# OOBD-Tiger_ISO-CAN.net
KiCad netlist of a schematic drawn in EAGLE
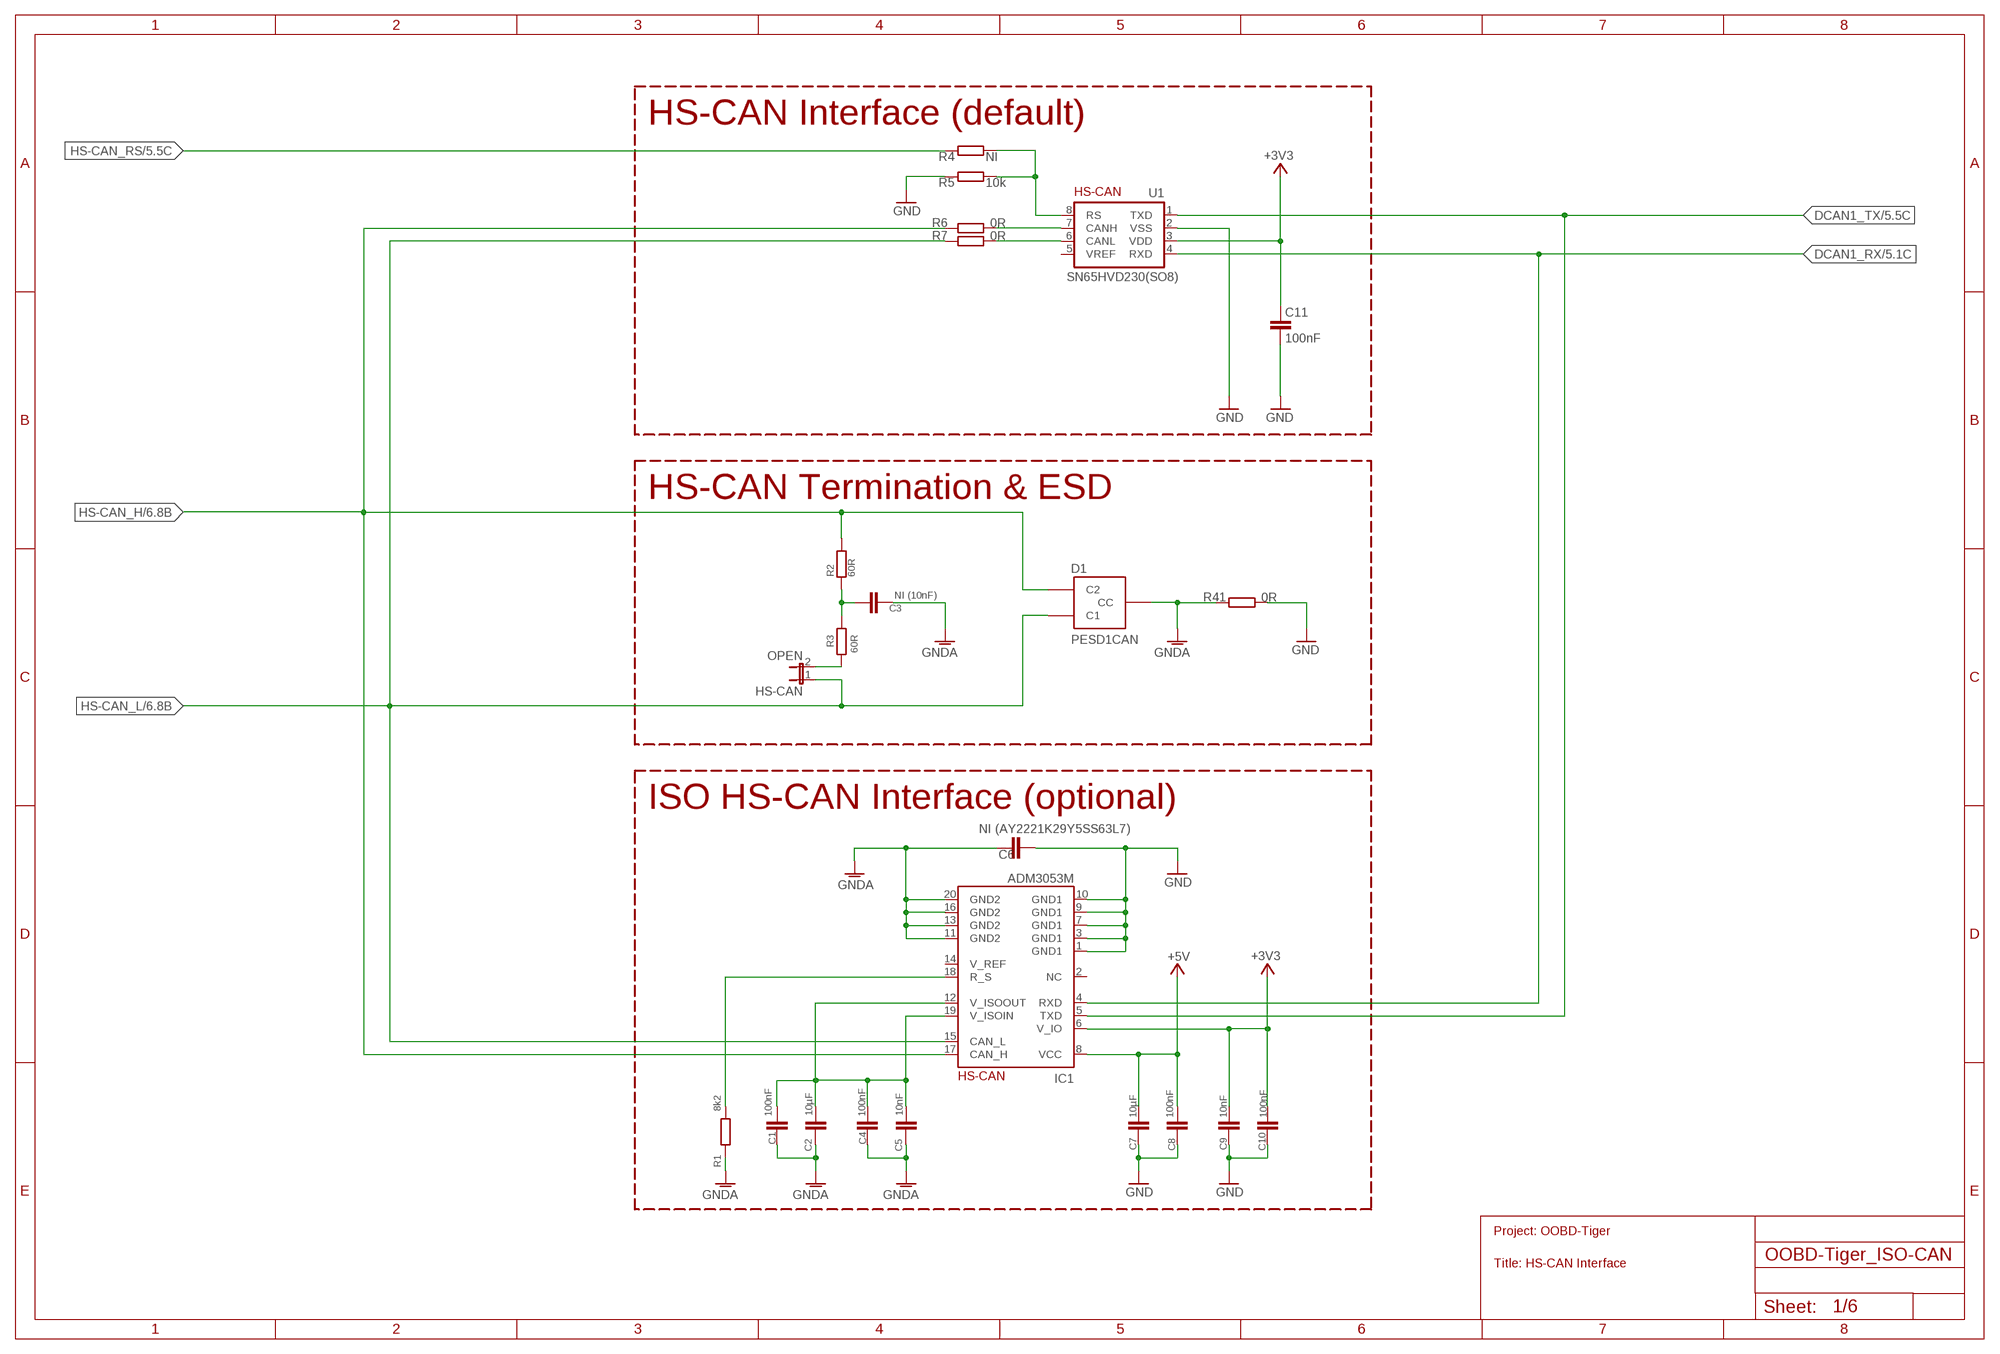
[diagram p0: schematic, sheet 1]
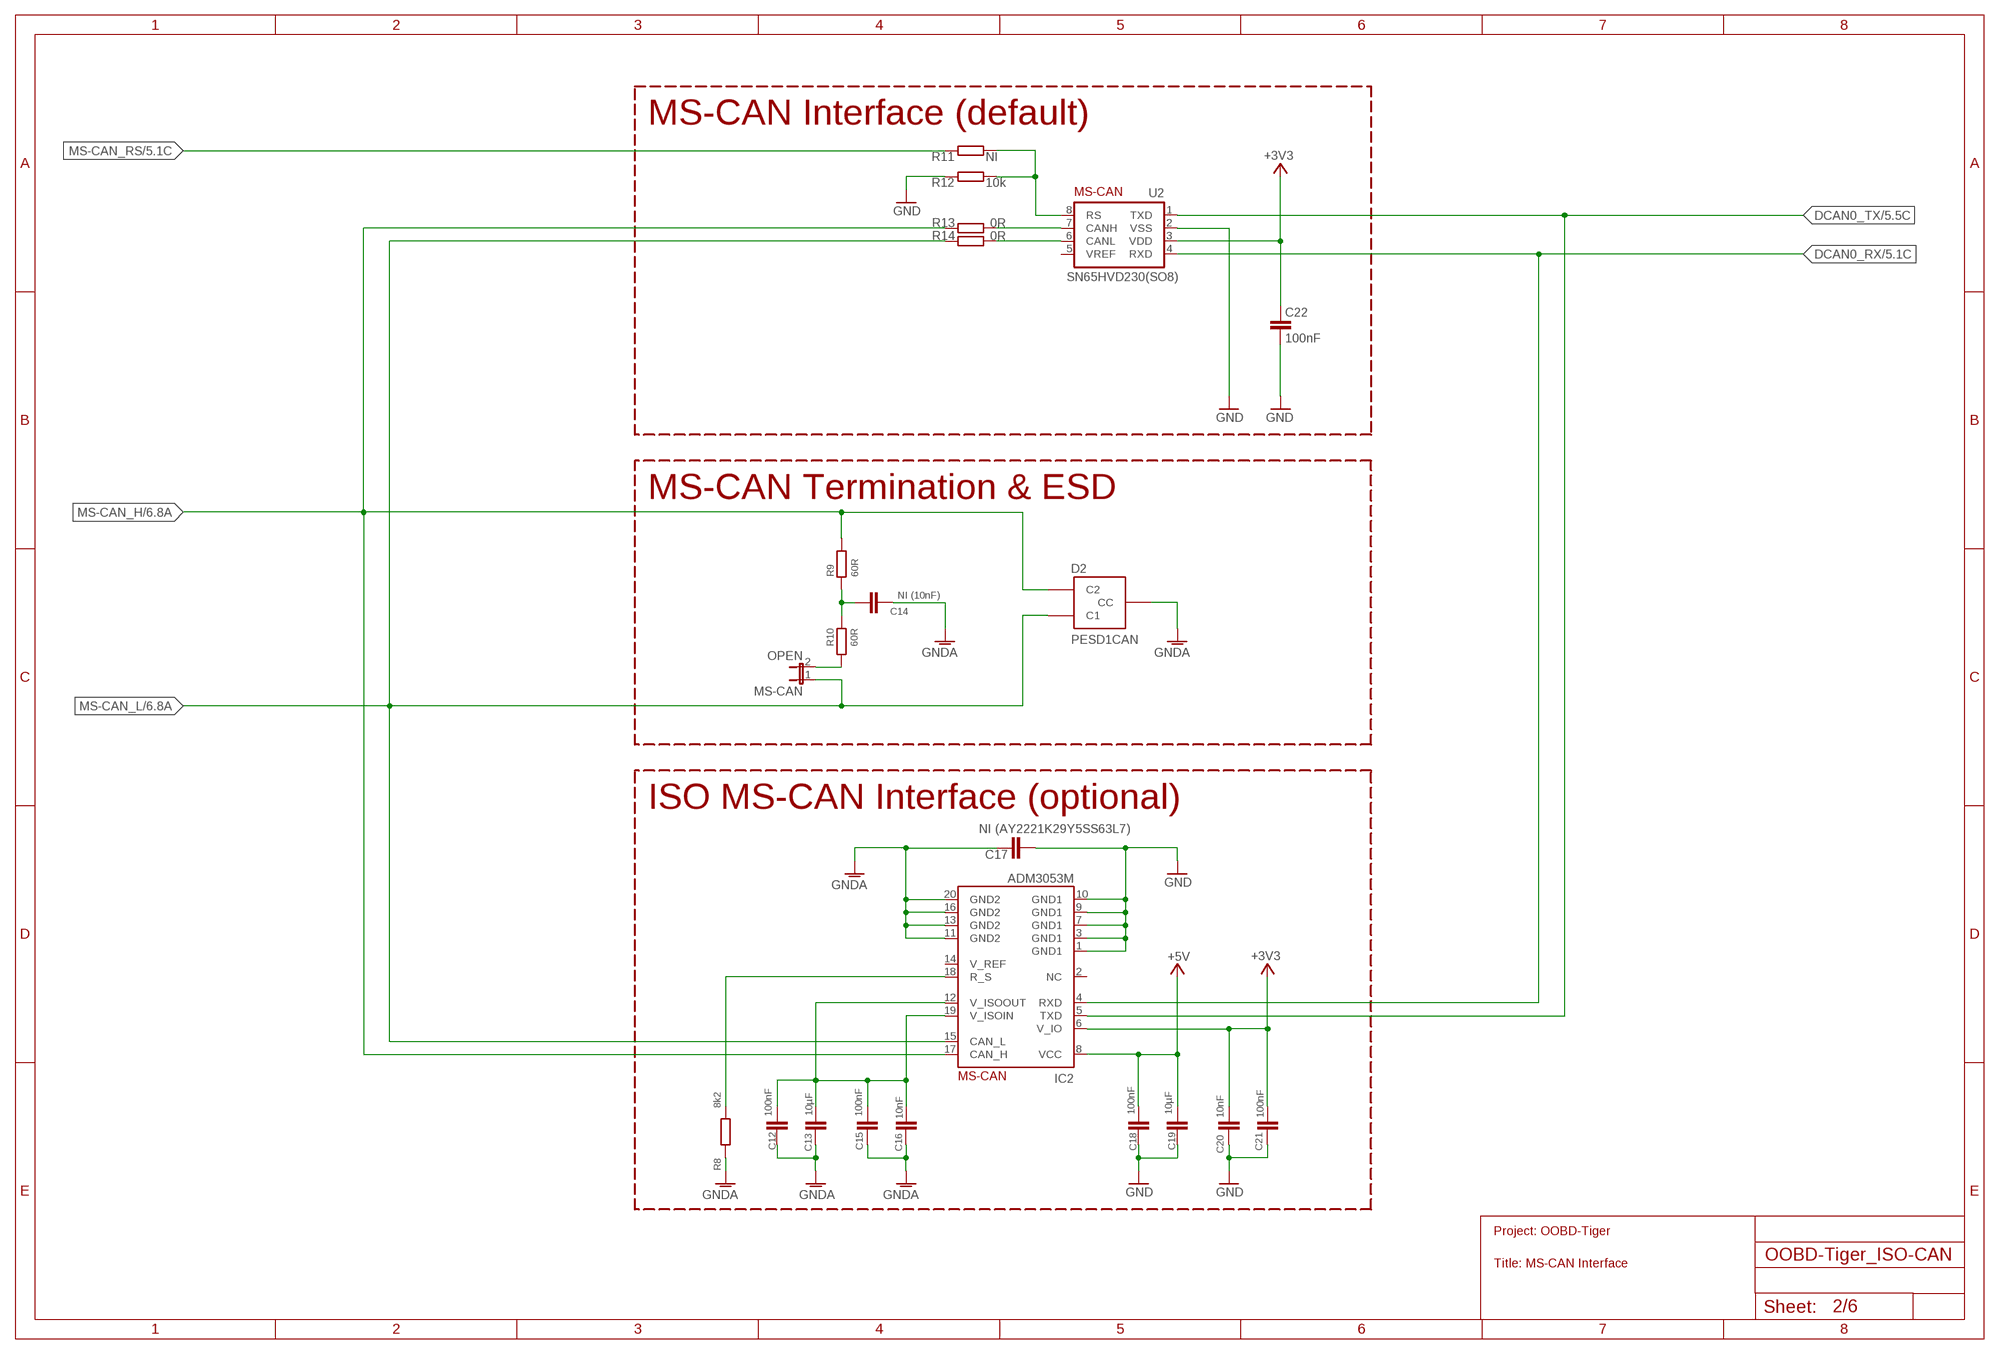
[diagram p1: schematic, sheet 2]
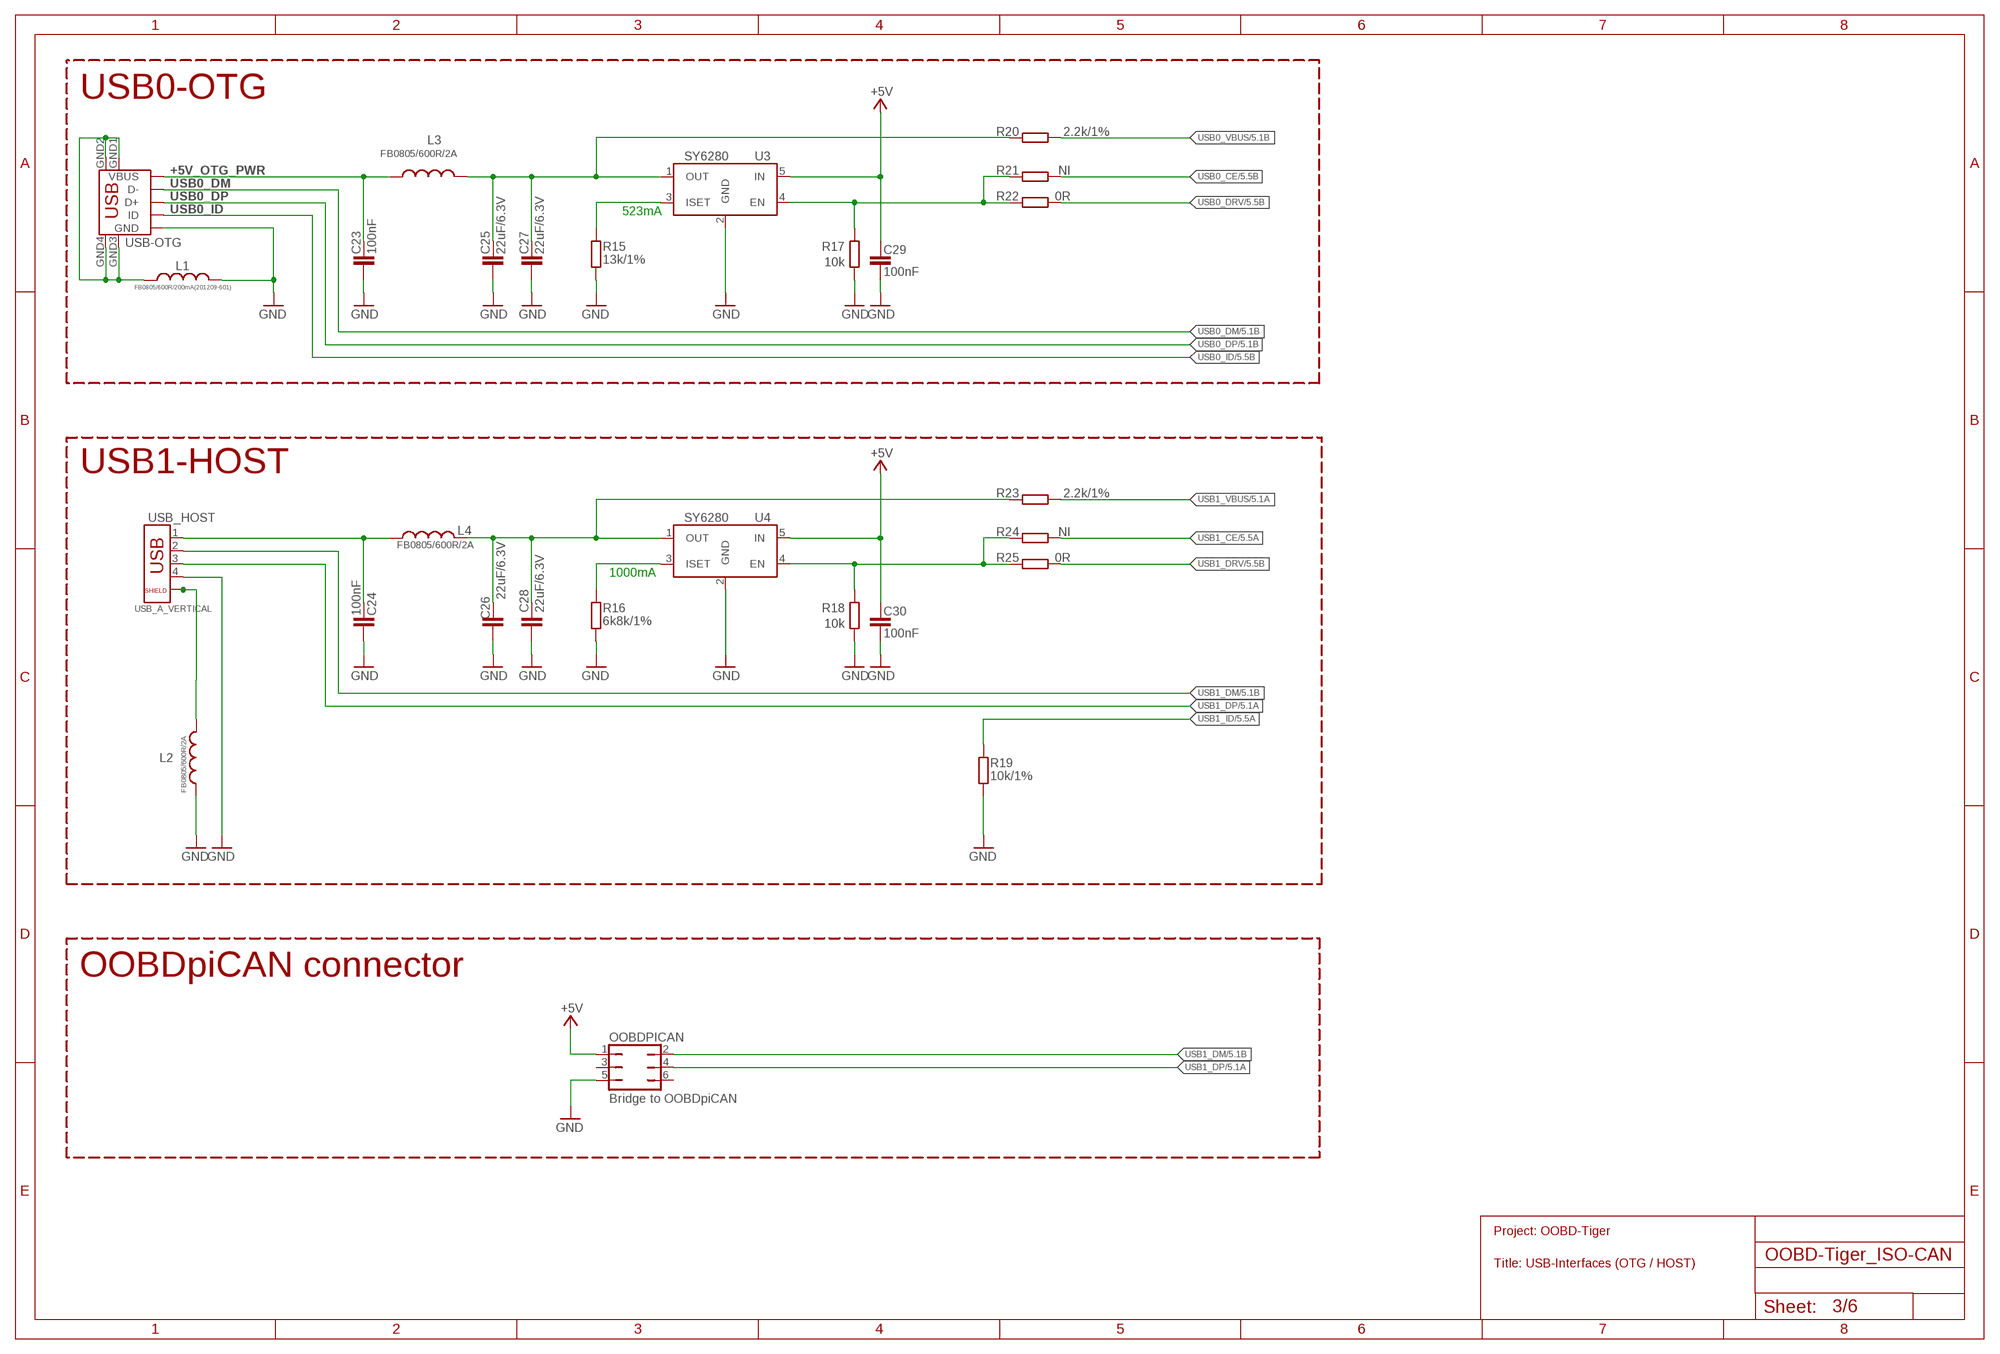
[diagram p2: schematic, sheet 3]
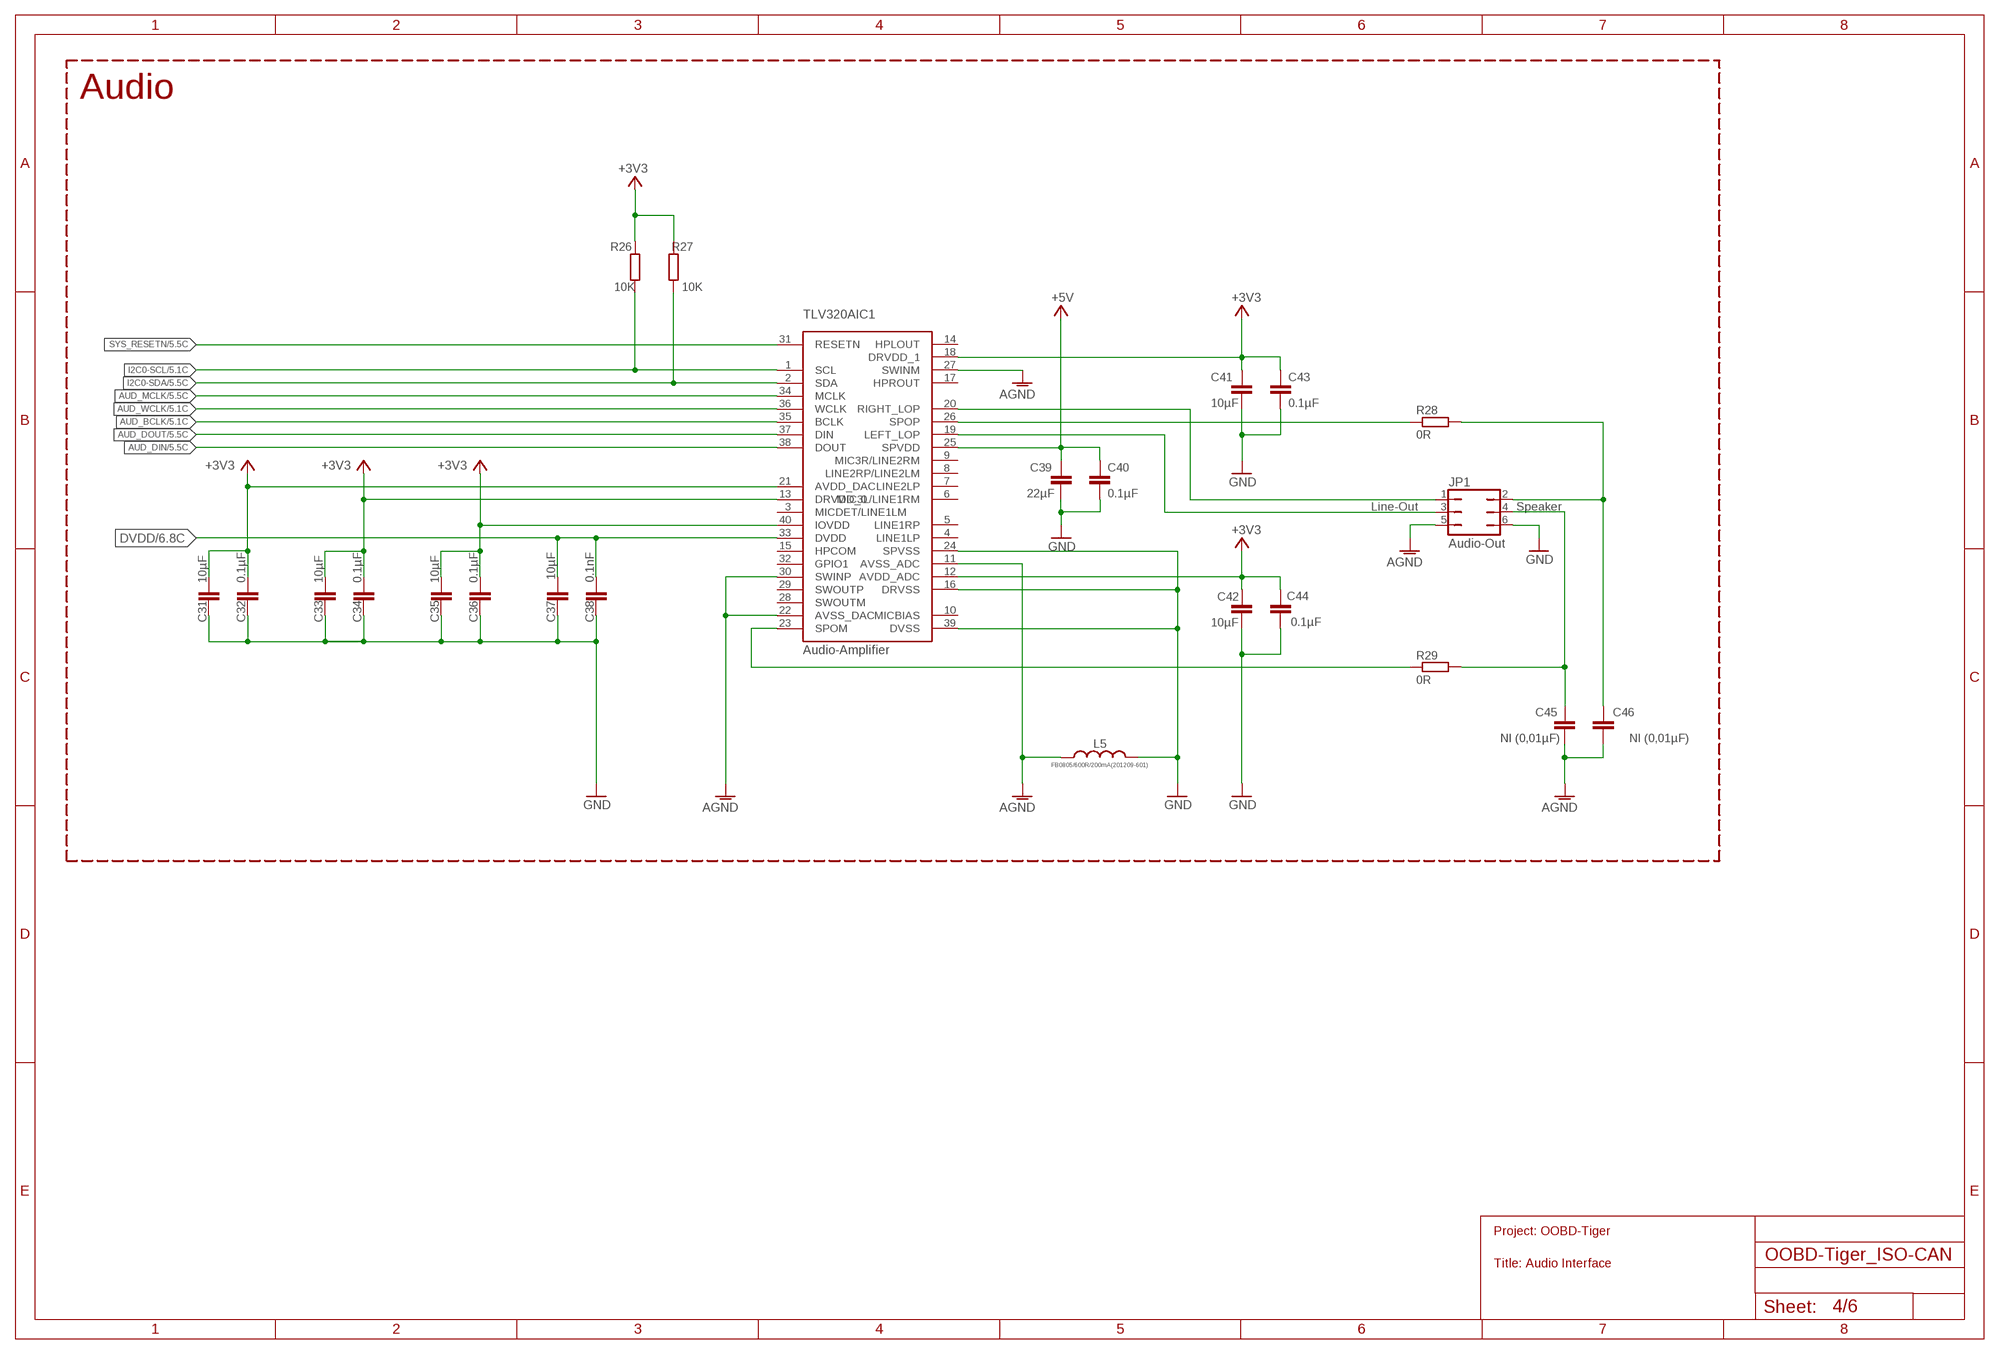
[diagram p3: schematic, sheet 4]
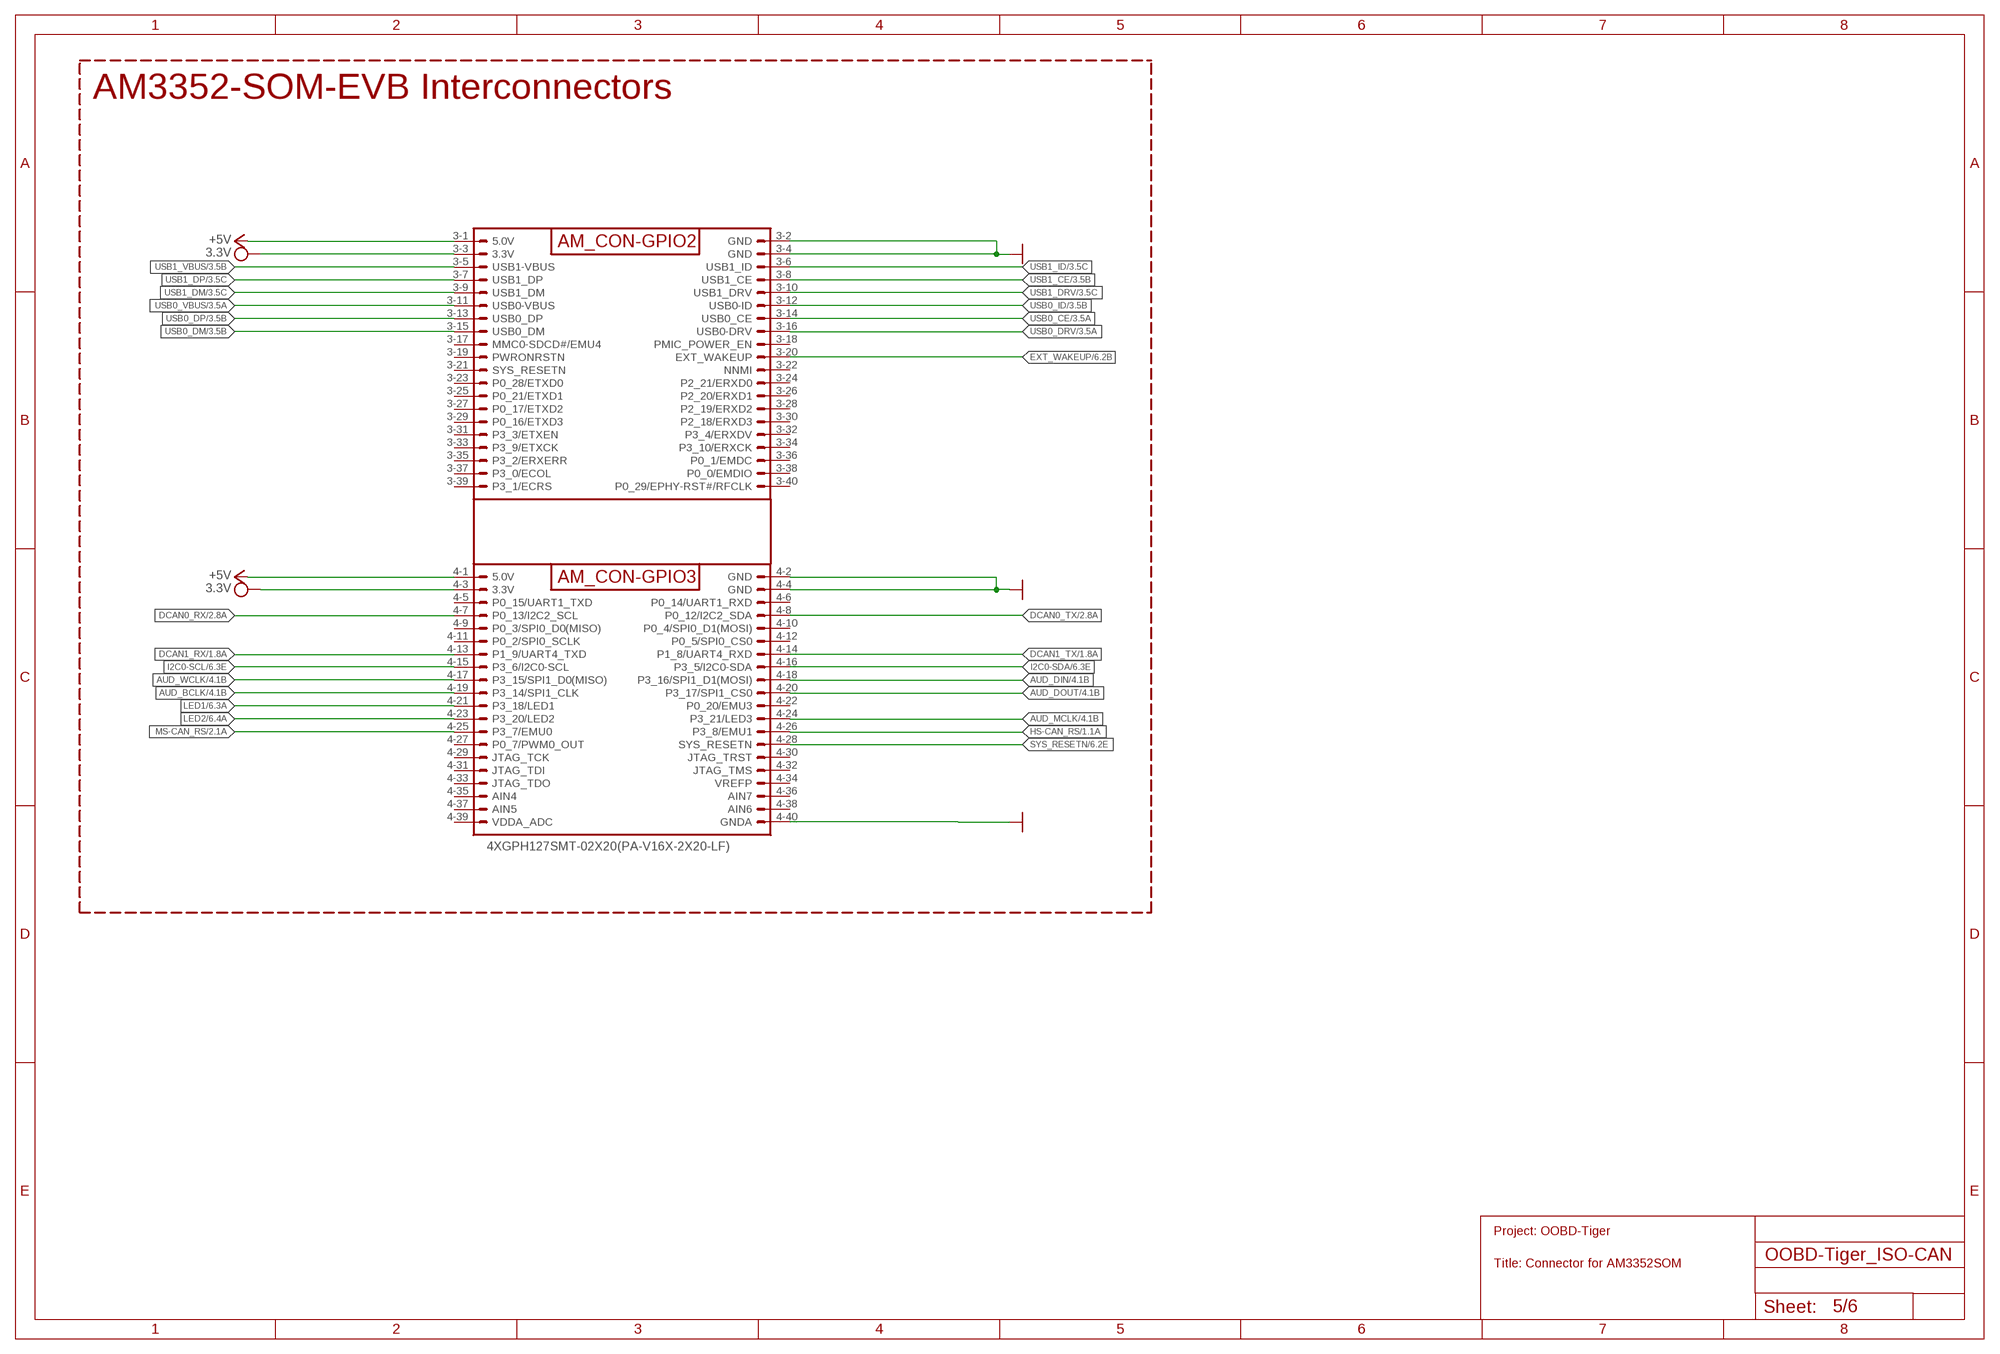
[diagram p4: schematic, sheet 5]
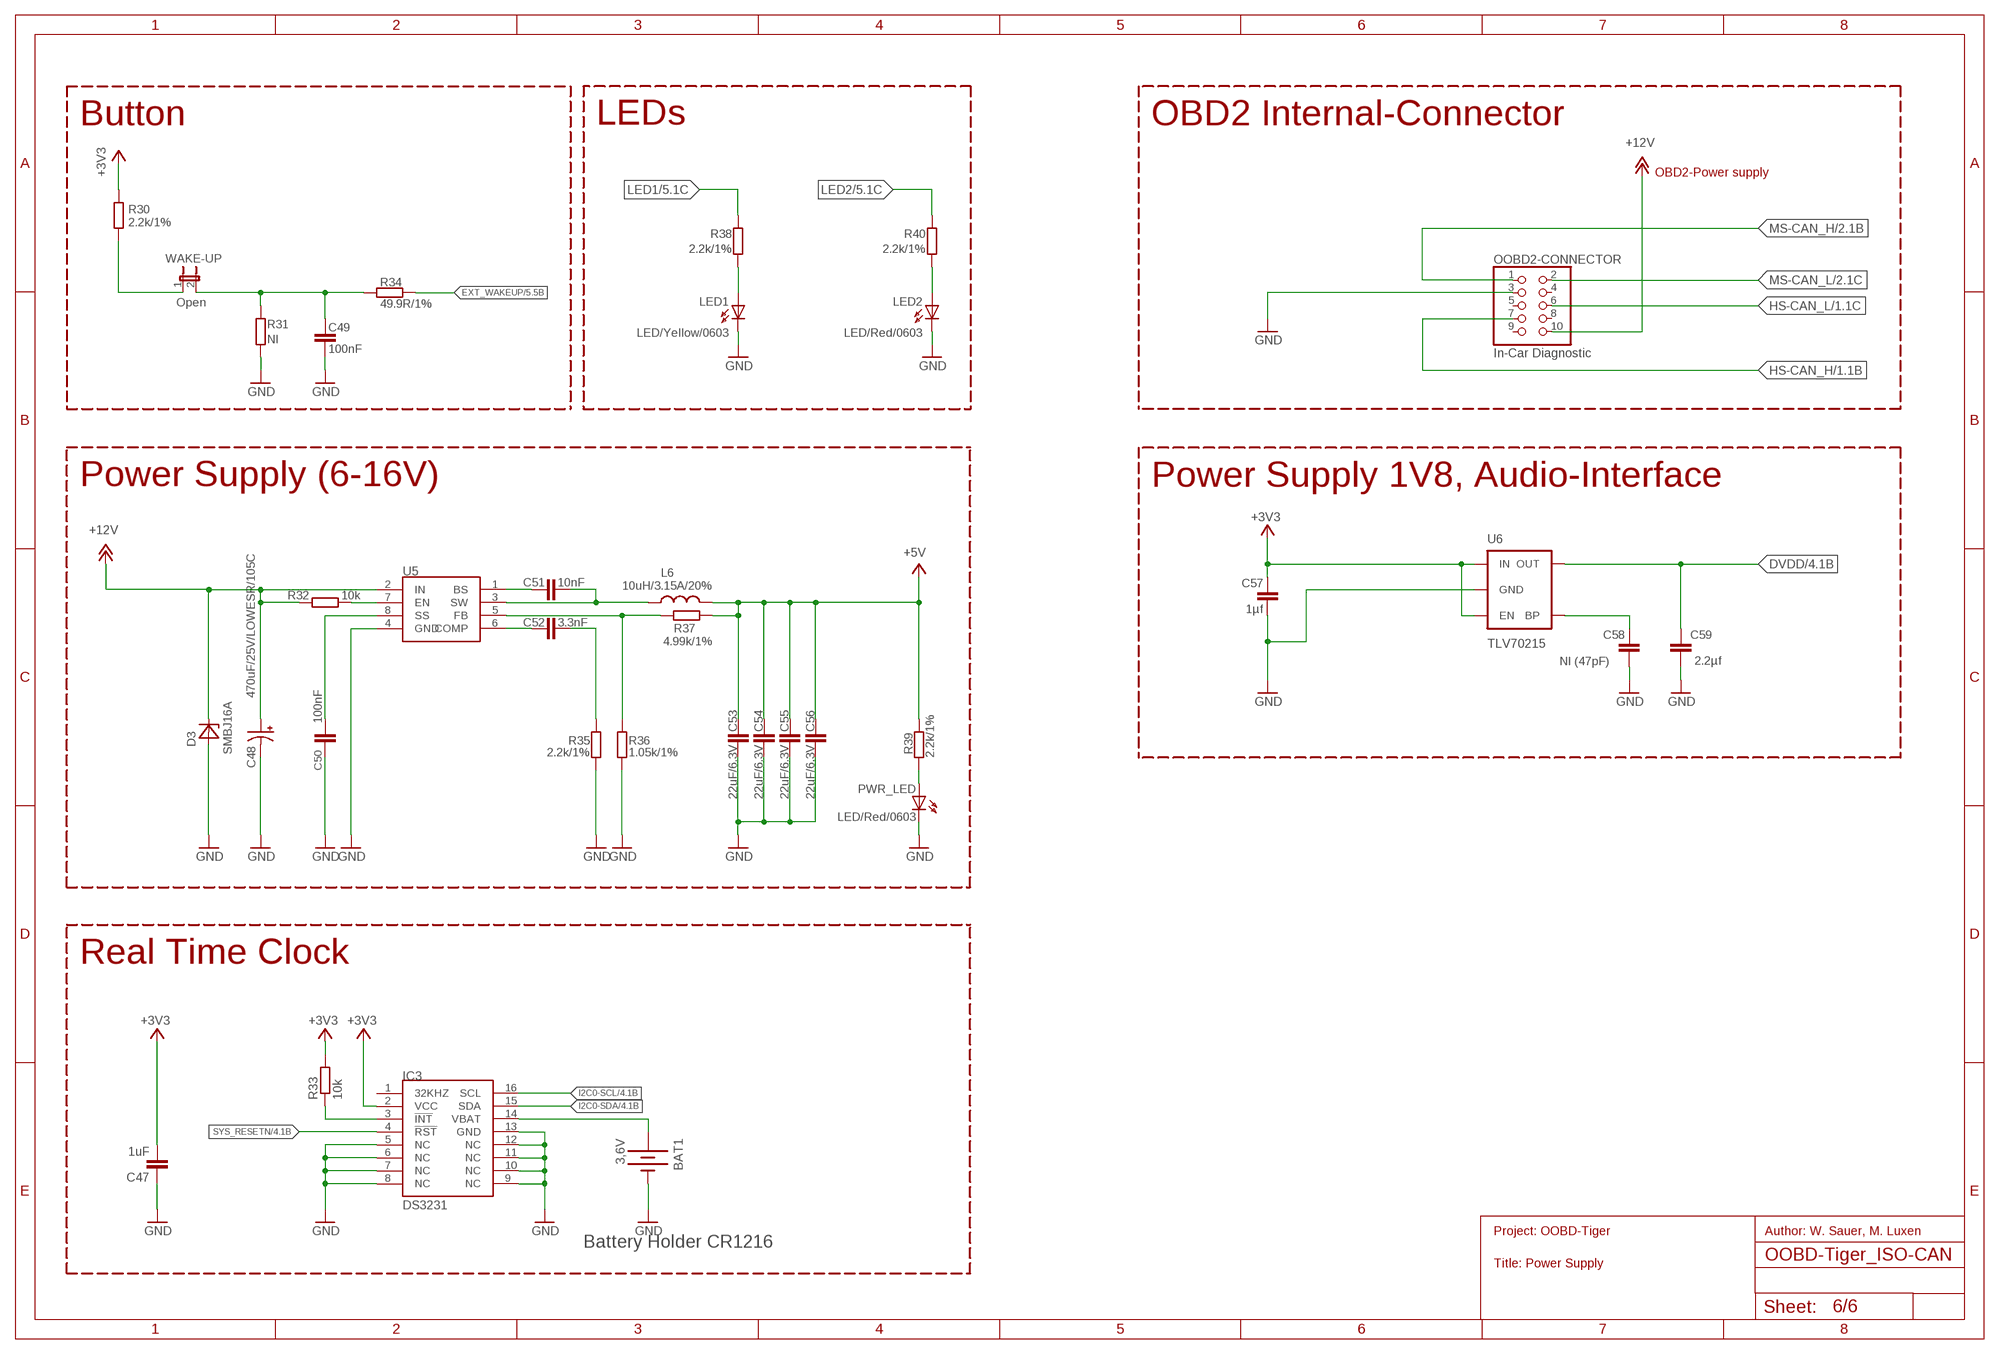
[diagram p5: schematic, sheet 6]

(export (version "E")
  (design (tool "Eeschema 10.0.6"))
  (components
    (comp (ref "C31")
      (value "10µF")
      (footprint "eagle-import:0603-CAP")
      (libsource (lib "eagle-import") (part "CAP0603-CAP"))
    )
    (comp (ref "C32")
      (value "0.1µF")
      (footprint "eagle-import:0603-CAP")
      (libsource (lib "eagle-import") (part "CAP0603-CAP"))
    )
    (comp (ref "C33")
      (value "10µF")
      (footprint "eagle-import:0603-CAP")
      (libsource (lib "eagle-import") (part "CAP0603-CAP"))
    )
    (comp (ref "C34")
      (value "0.1µF")
      (footprint "eagle-import:0603-CAP")
      (libsource (lib "eagle-import") (part "CAP0603-CAP"))
    )
    (comp (ref "C35")
      (value "10µF")
      (footprint "eagle-import:0603-CAP")
      (libsource (lib "eagle-import") (part "CAP0603-CAP"))
    )
    (comp (ref "C36")
      (value "0.1µF")
      (footprint "eagle-import:0603-CAP")
      (libsource (lib "eagle-import") (part "CAP0603-CAP"))
    )
    (comp (ref "C37")
      (value "10µF")
      (footprint "eagle-import:0603-CAP")
      (libsource (lib "eagle-import") (part "CAP0603-CAP"))
    )
    (comp (ref "C38")
      (value "0.1nF")
      (footprint "eagle-import:0603-CAP")
      (libsource (lib "eagle-import") (part "CAP0603-CAP"))
    )
    (comp (ref "C39")
      (value "22µF")
      (footprint "eagle-import:0603-CAP")
      (libsource (lib "eagle-import") (part "CAP0603-CAP"))
    )
    (comp (ref "C40")
      (value "0.1µF")
      (footprint "eagle-import:0603-CAP")
      (libsource (lib "eagle-import") (part "CAP0603-CAP"))
    )
    (comp (ref "C41")
      (value "10µF")
      (footprint "eagle-import:0603-CAP")
      (libsource (lib "eagle-import") (part "CAP0603-CAP"))
    )
    (comp (ref "C42")
      (value "10µF")
      (footprint "eagle-import:0603-CAP")
      (libsource (lib "eagle-import") (part "CAP0603-CAP"))
    )
    (comp (ref "C43")
      (value "0.1µF")
      (footprint "eagle-import:0603-CAP")
      (libsource (lib "eagle-import") (part "CAP0603-CAP"))
    )
    (comp (ref "C44")
      (value "0.1µF")
      (footprint "eagle-import:0603-CAP")
      (libsource (lib "eagle-import") (part "CAP0603-CAP"))
    )
    (comp (ref "C45")
      (value "NI (0,01µF)")
      (footprint "eagle-import:0603-CAP")
      (libsource (lib "eagle-import") (part "CAP0603-CAP"))
    )
    (comp (ref "C46")
      (value "NI (0,01µF)")
      (footprint "eagle-import:0603-CAP")
      (libsource (lib "eagle-import") (part "CAP0603-CAP"))
    )
    (comp (ref "JP1")
      (value "Audio-Out")
      (footprint "eagle-import:JP3Q")
      (libsource (lib "eagle-import") (part "JP3Q"))
    )
    (comp (ref "L5")
      (value "FB0805/600R/200mA(201209-601)")
      (footprint "eagle-import:L0603")
      (libsource (lib "eagle-import") (part "L-USL0603"))
    )
    (comp (ref "R26")
      (value "10K")
      (footprint "eagle-import:R0603")
      (libsource (lib "eagle-import") (part "resistor_R-EU_R0603"))
    )
    (comp (ref "R27")
      (value "10K")
      (footprint "eagle-import:R0603")
      (libsource (lib "eagle-import") (part "resistor_R-EU_R0603"))
    )
    (comp (ref "R28")
      (value "0R")
      (footprint "eagle-import:R0805")
      (libsource (lib "eagle-import") (part "resistor_R-EU_R0805"))
    )
    (comp (ref "R29")
      (value "0R")
      (footprint "eagle-import:R0805")
      (libsource (lib "eagle-import") (part "resistor_R-EU_R0805"))
    )
    (comp (ref "TLV320AIC1")
      (value "Audio-Amplifier")
      (footprint "eagle-import:QFN40-6X6")
      (libsource (lib "eagle-import") (part "TLV320AIC3107"))
    )
    (comp (ref "C1")
      (value "100nF")
      (footprint "eagle-import:C0603K")
      (libsource (lib "eagle-import") (part "C-EUC0603K"))
    )
    (comp (ref "C2")
      (value "10µF")
      (footprint "eagle-import:C0805K")
      (libsource (lib "eagle-import") (part "C-EUC0805K"))
    )
    (comp (ref "C3")
      (value "NI (10nF)")
      (footprint "eagle-import:C0603")
      (libsource (lib "eagle-import") (part "resistor_C-EUC0603"))
    )
    (comp (ref "C4")
      (value "100nF")
      (footprint "eagle-import:C0603K")
      (libsource (lib "eagle-import") (part "C-EUC0603K"))
    )
    (comp (ref "C5")
      (value "10nF")
      (footprint "eagle-import:C0805K")
      (libsource (lib "eagle-import") (part "C-EUC0805K"))
    )
    (comp (ref "C6")
      (value "NI (AY2221K29Y5SS63L7)")
      (footprint "eagle-import:C075-032X103")
      (libsource (lib "eagle-import") (part "C-EU075-032X103"))
    )
    (comp (ref "C7")
      (value "10µF")
      (footprint "eagle-import:C0805K")
      (libsource (lib "eagle-import") (part "C-EUC0805K"))
    )
    (comp (ref "C8")
      (value "100nF")
      (footprint "eagle-import:C0603K")
      (libsource (lib "eagle-import") (part "C-EUC0603K"))
    )
    (comp (ref "C9")
      (value "10nF")
      (footprint "eagle-import:C0805K")
      (libsource (lib "eagle-import") (part "C-EUC0805K"))
    )
    (comp (ref "C10")
      (value "100nF")
      (footprint "eagle-import:C0603K")
      (libsource (lib "eagle-import") (part "C-EUC0603K"))
    )
    (comp (ref "C11")
      (value "100nF")
      (footprint "eagle-import:C0603K")
      (libsource (lib "eagle-import") (part "C-EUC0603K"))
    )
    (comp (ref "D1")
      (value "PESD1CAN")
      (footprint "eagle-import:SOT23")
      (libsource (lib "eagle-import") (part "PESD1CAN"))
    )
    (comp (ref "HS-CAN")
      (value "OPEN")
      (footprint "eagle-import:1X02")
      (libsource (lib "eagle-import") (part "JUMPER-2PTH"))
    )
    (comp (ref "IC1")
      (value "ADM3053M")
      (footprint "eagle-import:SO20W")
      (libsource (lib "eagle-import") (part "ADM3053M"))
    )
    (comp (ref "R1")
      (value "8k2")
      (footprint "eagle-import:R0603")
      (libsource (lib "eagle-import") (part "R-EU_R0603"))
    )
    (comp (ref "R2")
      (value "60R")
      (footprint "eagle-import:R0603")
      (libsource (lib "eagle-import") (part "resistor_R-EU_R0603"))
    )
    (comp (ref "R3")
      (value "60R")
      (footprint "eagle-import:R0603")
      (libsource (lib "eagle-import") (part "resistor_R-EU_R0603"))
    )
    (comp (ref "R4")
      (value "NI")
      (footprint "eagle-import:R0603")
      (libsource (lib "eagle-import") (part "R-EU_R0603"))
    )
    (comp (ref "R5")
      (value "10k")
      (footprint "eagle-import:R0603")
      (libsource (lib "eagle-import") (part "R-EU_R0603"))
    )
    (comp (ref "R6")
      (value "0R")
      (footprint "eagle-import:0207_10")
      (libsource (lib "eagle-import") (part "R-EU_0207/10"))
    )
    (comp (ref "R7")
      (value "0R")
      (footprint "eagle-import:0207_10")
      (libsource (lib "eagle-import") (part "R-EU_0207/10"))
    )
    (comp (ref "R41")
      (value "0R")
      (footprint "eagle-import:0207_10")
      (libsource (lib "eagle-import") (part "R-EU_0207/10"))
    )
    (comp (ref "U1")
      (value "SN65HVD230(SO8)")
      (footprint "eagle-import:SO-08")
      (libsource (lib "eagle-import") (part "MCP2551"))
    )
    (comp (ref "C23")
      (value "100nF")
      (footprint "eagle-import:C0603K")
      (libsource (lib "eagle-import") (part "C-EUC0603K"))
    )
    (comp (ref "C24")
      (value "100nF")
      (footprint "eagle-import:C0603K")
      (libsource (lib "eagle-import") (part "C-EUC0603K"))
    )
    (comp (ref "C25")
      (value "22uF/6.3V")
      (footprint "eagle-import:C0603")
      (libsource (lib "eagle-import") (part "C-EUC0603"))
    )
    (comp (ref "C26")
      (value "22uF/6.3V")
      (footprint "eagle-import:C0603")
      (libsource (lib "eagle-import") (part "C-EUC0603"))
    )
    (comp (ref "C27")
      (value "22uF/6.3V")
      (footprint "eagle-import:C0603")
      (libsource (lib "eagle-import") (part "C-EUC0603"))
    )
    (comp (ref "C28")
      (value "22uF/6.3V")
      (footprint "eagle-import:C0603")
      (libsource (lib "eagle-import") (part "C-EUC0603"))
    )
    (comp (ref "C29")
      (value "100nF")
      (footprint "eagle-import:C0603K")
      (libsource (lib "eagle-import") (part "C-EUC0603K"))
    )
    (comp (ref "C30")
      (value "100nF")
      (footprint "eagle-import:C0603K")
      (libsource (lib "eagle-import") (part "C-EUC0603K"))
    )
    (comp (ref "L1")
      (value "FB0805/600R/200mA(201209-601)")
      (footprint "eagle-import:L0603")
      (libsource (lib "eagle-import") (part "L-USL0603"))
    )
    (comp (ref "L2")
      (value "FB0805/600R/2A")
      (footprint "eagle-import:L0603")
      (libsource (lib "eagle-import") (part "L-USL0603"))
    )
    (comp (ref "L3")
      (value "FB0805/600R/2A")
      (footprint "eagle-import:L0603")
      (libsource (lib "eagle-import") (part "L-USL0603"))
    )
    (comp (ref "L4")
      (value "FB0805/600R/2A")
      (footprint "eagle-import:L0603")
      (libsource (lib "eagle-import") (part "L-USL0603"))
    )
    (comp (ref "OOBDPICAN")
      (value "Bridge to OOBDpiCAN")
      (footprint "eagle-import:JP3Q")
      (libsource (lib "eagle-import") (part "JP3Q"))
    )
    (comp (ref "R15")
      (value "13k/1%")
      (footprint "eagle-import:R0603")
      (libsource (lib "eagle-import") (part "R-EU_R0603"))
    )
    (comp (ref "R16")
      (value "6k8k/1%")
      (footprint "eagle-import:R0603")
      (libsource (lib "eagle-import") (part "R-EU_R0603"))
    )
    (comp (ref "R17")
      (value "10k")
      (footprint "eagle-import:R0603")
      (libsource (lib "eagle-import") (part "R-EU_R0603"))
    )
    (comp (ref "R18")
      (value "10k")
      (footprint "eagle-import:R0603")
      (libsource (lib "eagle-import") (part "R-EU_R0603"))
    )
    (comp (ref "R19")
      (value "10k/1%")
      (footprint "eagle-import:R0603")
      (libsource (lib "eagle-import") (part "R-EU_R0603"))
    )
    (comp (ref "R20")
      (value "2.2k/1%")
      (footprint "eagle-import:R0603")
      (libsource (lib "eagle-import") (part "R-EU_R0603"))
    )
    (comp (ref "R21")
      (value "NI")
      (footprint "eagle-import:R0603")
      (libsource (lib "eagle-import") (part "R-EU_R0603"))
    )
    (comp (ref "R22")
      (value "0R")
      (footprint "eagle-import:R0603")
      (libsource (lib "eagle-import") (part "R-EU_R0603"))
    )
    (comp (ref "R23")
      (value "2.2k/1%")
      (footprint "eagle-import:R0603")
      (libsource (lib "eagle-import") (part "R-EU_R0603"))
    )
    (comp (ref "R24")
      (value "NI")
      (footprint "eagle-import:R0603")
      (libsource (lib "eagle-import") (part "R-EU_R0603"))
    )
    (comp (ref "R25")
      (value "0R")
      (footprint "eagle-import:R0603")
      (libsource (lib "eagle-import") (part "R-EU_R0603"))
    )
    (comp (ref "U3")
      (value "SY6280")
      (footprint "eagle-import:SOT23-5")
      (libsource (lib "eagle-import") (part "SY6280"))
    )
    (comp (ref "U4")
      (value "SY6280")
      (footprint "eagle-import:SOT23-5")
      (libsource (lib "eagle-import") (part "SY6280"))
    )
    (comp (ref "USB_HOST")
      (value "USB_A_VERTICAL")
      (footprint "eagle-import:USB_PN87520_DEV_PTH")
      (libsource (lib "eagle-import") (part "USB_SHIELD1"))
    )
    (comp (ref "USB_OTG")
      (value "USB-OTG")
      (footprint "eagle-import:USB_MINI_9PIN")
      (libsource (lib "eagle-import") (part "MINI_USB9"))
    )
    (comp (ref "C12")
      (value "100nF")
      (footprint "eagle-import:C0603K")
      (libsource (lib "eagle-import") (part "C-EUC0603K"))
    )
    (comp (ref "C13")
      (value "10µF")
      (footprint "eagle-import:C0805K")
      (libsource (lib "eagle-import") (part "C-EUC0805K"))
    )
    (comp (ref "C14")
      (value "NI (10nF)")
      (footprint "eagle-import:C0603")
      (libsource (lib "eagle-import") (part "resistor_C-EUC0603"))
    )
    (comp (ref "C15")
      (value "100nF")
      (footprint "eagle-import:C0603K")
      (libsource (lib "eagle-import") (part "C-EUC0603K"))
    )
    (comp (ref "C16")
      (value "10nF")
      (footprint "eagle-import:C0805K")
      (libsource (lib "eagle-import") (part "C-EUC0805K"))
    )
    (comp (ref "C17")
      (value "NI (AY2221K29Y5SS63L7)")
      (footprint "eagle-import:C075-032X103")
      (libsource (lib "eagle-import") (part "C-EU075-032X103"))
    )
    (comp (ref "C18")
      (value "100nF")
      (footprint "eagle-import:C0603K")
      (libsource (lib "eagle-import") (part "C-EUC0603K"))
    )
    (comp (ref "C19")
      (value "10µF")
      (footprint "eagle-import:C0805K")
      (libsource (lib "eagle-import") (part "C-EUC0805K"))
    )
    (comp (ref "C20")
      (value "10nF")
      (footprint "eagle-import:C0805K")
      (libsource (lib "eagle-import") (part "C-EUC0805K"))
    )
    (comp (ref "C21")
      (value "100nF")
      (footprint "eagle-import:C0603K")
      (libsource (lib "eagle-import") (part "C-EUC0603K"))
    )
    (comp (ref "C22")
      (value "100nF")
      (footprint "eagle-import:C0603K")
      (libsource (lib "eagle-import") (part "C-EUC0603K"))
    )
    (comp (ref "D2")
      (value "PESD1CAN")
      (footprint "eagle-import:SOT23")
      (libsource (lib "eagle-import") (part "PESD1CAN"))
    )
    (comp (ref "IC2")
      (value "ADM3053M")
      (footprint "eagle-import:SO20W")
      (libsource (lib "eagle-import") (part "ADM3053M"))
    )
    (comp (ref "MS-CAN")
      (value "OPEN")
      (footprint "eagle-import:1X02")
      (libsource (lib "eagle-import") (part "JUMPER-2PTH"))
    )
    (comp (ref "R8")
      (value "8k2")
      (footprint "eagle-import:R0603")
      (libsource (lib "eagle-import") (part "R-EU_R0603"))
    )
    (comp (ref "R9")
      (value "60R")
      (footprint "eagle-import:R0603")
      (libsource (lib "eagle-import") (part "resistor_R-EU_R0603"))
    )
    (comp (ref "R10")
      (value "60R")
      (footprint "eagle-import:R0603")
      (libsource (lib "eagle-import") (part "resistor_R-EU_R0603"))
    )
    (comp (ref "R11")
      (value "NI")
      (footprint "eagle-import:R0603")
      (libsource (lib "eagle-import") (part "R-EU_R0603"))
    )
    (comp (ref "R12")
      (value "10k")
      (footprint "eagle-import:R0603")
      (libsource (lib "eagle-import") (part "R-EU_R0603"))
    )
    (comp (ref "R13")
      (value "0R")
      (footprint "eagle-import:0207_10")
      (libsource (lib "eagle-import") (part "R-EU_0207/10"))
    )
    (comp (ref "R14")
      (value "0R")
      (footprint "eagle-import:0207_10")
      (libsource (lib "eagle-import") (part "R-EU_0207/10"))
    )
    (comp (ref "U2")
      (value "SN65HVD230(SO8)")
      (footprint "eagle-import:SO-08")
      (libsource (lib "eagle-import") (part "MCP2551"))
    )
    (comp (ref "BAT1")
      (value "3,6V")
      (footprint "eagle-import:BATTCON_12MM_PTH")
      (libsource (lib "eagle-import") (part "BATTERY12PTH"))
    )
    (comp (ref "C47")
      (value "1uF")
      (footprint "eagle-import:C0603")
      (libsource (lib "eagle-import") (part "C-EUC0603"))
    )
    (comp (ref "C48")
      (value "470uF/25V/LOWESR/105C")
      (footprint "eagle-import:PANASONIC_D")
      (libsource (lib "eagle-import") (part "47UF-50V-20%(ELECT)"))
    )
    (comp (ref "C49")
      (value "100nF")
      (footprint "eagle-import:C0603")
      (libsource (lib "eagle-import") (part "C-EUC0603"))
    )
    (comp (ref "C50")
      (value "100nF")
      (footprint "eagle-import:C0603")
      (libsource (lib "eagle-import") (part "C-EUC0603"))
    )
    (comp (ref "C51")
      (value "10nF")
      (footprint "eagle-import:C0603")
      (libsource (lib "eagle-import") (part "C-EUC0603"))
    )
    (comp (ref "C52")
      (value "3.3nF")
      (footprint "eagle-import:C0603")
      (libsource (lib "eagle-import") (part "C-EUC0603"))
    )
    (comp (ref "C53")
      (value "22uF/6.3V")
      (footprint "eagle-import:C0603")
      (libsource (lib "eagle-import") (part "C-EUC0603"))
    )
    (comp (ref "C54")
      (value "22uF/6.3V")
      (footprint "eagle-import:C0603")
      (libsource (lib "eagle-import") (part "C-EUC0603"))
    )
    (comp (ref "C55")
      (value "22uF/6.3V")
      (footprint "eagle-import:C0603")
      (libsource (lib "eagle-import") (part "C-EUC0603"))
    )
    (comp (ref "C56")
      (value "22uF/6.3V")
      (footprint "eagle-import:C0603")
      (libsource (lib "eagle-import") (part "C-EUC0603"))
    )
    (comp (ref "C57")
      (value "1µf")
      (footprint "eagle-import:0603-CAP")
      (libsource (lib "eagle-import") (part "CAP0603-CAP"))
    )
    (comp (ref "C58")
      (value "NI (47pF)")
      (footprint "eagle-import:0603-CAP")
      (libsource (lib "eagle-import") (part "CAP0603-CAP"))
    )
    (comp (ref "C59")
      (value "2.2µf")
      (footprint "eagle-import:0603-CAP")
      (libsource (lib "eagle-import") (part "CAP0603-CAP"))
    )
    (comp (ref "D3")
      (value "SMBJ16A")
      (footprint "eagle-import:DO214AA")
      (libsource (lib "eagle-import") (part "SMBJ16A"))
    )
    (comp (ref "IC3")
      (value "DS3231")
      (footprint "eagle-import:SOIC-16W")
      (libsource (lib "eagle-import") (part "DS3231SOIC-16W"))
    )
    (comp (ref "L6")
      (value "10uH/3.15A/20%")
      (footprint "eagle-import:8X8MM_3131")
      (libsource (lib "eagle-import") (part "LLQH88PN100M38"))
    )
    (comp (ref "LED1")
      (value "LED/Yellow/0603")
      (footprint "eagle-import:LED_0603")
      (libsource (lib "eagle-import") (part "LEDLED_0603"))
    )
    (comp (ref "LED2")
      (value "LED/Red/0603")
      (footprint "eagle-import:LED_0603")
      (libsource (lib "eagle-import") (part "LEDLED_0603"))
    )
    (comp (ref "OOBD2-CONNECTOR")
      (value "In-Car Diagnostic")
      (footprint "eagle-import:2X05_90")
      (libsource (lib "eagle-import") (part "PINHD-2X5/90"))
    )
    (comp (ref "PWR_LED")
      (value "LED/Red/0603")
      (footprint "eagle-import:LED-0603")
      (libsource (lib "eagle-import") (part "LED0603DWS"))
    )
    (comp (ref "R30")
      (value "2.2k/1%")
      (footprint "eagle-import:R0603")
      (libsource (lib "eagle-import") (part "R-EU_R0603"))
    )
    (comp (ref "R31")
      (value "NI")
      (footprint "eagle-import:R0603")
      (libsource (lib "eagle-import") (part "R-EU_R0603"))
    )
    (comp (ref "R32")
      (value "10k")
      (footprint "eagle-import:R0603")
      (libsource (lib "eagle-import") (part "R-EU_R0603"))
    )
    (comp (ref "R33")
      (value "10k")
      (footprint "eagle-import:R0603")
      (libsource (lib "eagle-import") (part "R-EU_R0603"))
    )
    (comp (ref "R34")
      (value "49.9R/1%")
      (footprint "eagle-import:R0603")
      (libsource (lib "eagle-import") (part "R-EU_R0603"))
    )
    (comp (ref "R35")
      (value "2.2k/1%")
      (footprint "eagle-import:R0603")
      (libsource (lib "eagle-import") (part "R-EU_R0603"))
    )
    (comp (ref "R36")
      (value "1.05k/1%")
      (footprint "eagle-import:R0603")
      (libsource (lib "eagle-import") (part "R-EU_R0603"))
    )
    (comp (ref "R37")
      (value "4.99k/1%")
      (footprint "eagle-import:R0603")
      (libsource (lib "eagle-import") (part "R-EU_R0603"))
    )
    (comp (ref "R38")
      (value "2.2k/1%")
      (footprint "eagle-import:R0603")
      (libsource (lib "eagle-import") (part "R-EU_R0603"))
    )
    (comp (ref "R39")
      (value "2.2k/1%")
      (footprint "eagle-import:R0603")
      (libsource (lib "eagle-import") (part "R-EU_R0603"))
    )
    (comp (ref "R40")
      (value "2.2k/1%")
      (footprint "eagle-import:R0603")
      (libsource (lib "eagle-import") (part "R-EU_R0603"))
    )
    (comp (ref "U5")
      (value "MP1482")
      (footprint "eagle-import:SOIC8")
      (libsource (lib "eagle-import") (part "MP1482"))
    )
    (comp (ref "U6")
      (value "TLV70215")
      (footprint "eagle-import:SOT23-5")
      (libsource (lib "eagle-import") (part "V_REG_LDOSMD"))
    )
    (comp (ref "WAKE-UP")
      (value "Open")
      (footprint "eagle-import:1X02_LOCK")
      (libsource (lib "eagle-import") (part "JUMPER-2PTH_LOCK"))
    )
    (comp (ref "AM3352-SOM-EVB-PLATFORM")
      (value "4XGPH127SMT-02X20(PA-V16X-2X20-LF)")
      (footprint "eagle-import:OOBD-TIGER-AM3352-SOM")
      (libsource (lib "eagle-import") (part "OOBD-TIGER-AM3352-SOM---4XGPH127SMT-02X20(PA-V16X-2X20-LF)"))
    )
  )
  (nets
    (net (code "1") (name "+3V3") (class "Default")
      (node (ref "C10") (pin "1") (pinfunction "1_1") (pintype "passive"))
      (node (ref "C11") (pin "1") (pinfunction "1_1") (pintype "passive"))
      (node (ref "C20") (pin "1") (pinfunction "1_1") (pintype "passive"))
      (node (ref "C21") (pin "1") (pinfunction "1_1") (pintype "passive"))
      (node (ref "C22") (pin "1") (pinfunction "1_1") (pintype "passive"))
      (node (ref "C31") (pin "2") (pinfunction "2_2") (pintype "passive"))
      (node (ref "C32") (pin "2") (pinfunction "2_2") (pintype "passive"))
      (node (ref "C33") (pin "2") (pinfunction "2_2") (pintype "passive"))
      (node (ref "C34") (pin "2") (pinfunction "2_2") (pintype "passive"))
      (node (ref "C35") (pin "2") (pinfunction "2_2") (pintype "passive"))
      (node (ref "C36") (pin "2") (pinfunction "2_2") (pintype "passive"))
      (node (ref "C41") (pin "1") (pinfunction "1_1") (pintype "passive"))
      (node (ref "C42") (pin "1") (pinfunction "1_1") (pintype "passive"))
      (node (ref "C43") (pin "1") (pinfunction "1_1") (pintype "passive"))
      (node (ref "C44") (pin "1") (pinfunction "1_1") (pintype "passive"))
      (node (ref "C47") (pin "2") (pinfunction "2_2") (pintype "passive"))
      (node (ref "C57") (pin "2") (pinfunction "2_2") (pintype "passive"))
      (node (ref "C9") (pin "1") (pinfunction "1_1") (pintype "passive"))
      (node (ref "IC1") (pin "6") (pinfunction "V_IO_6") (pintype "power_in"))
      (node (ref "IC2") (pin "6") (pinfunction "V_IO_6") (pintype "power_in"))
      (node (ref "IC3") (pin "2") (pinfunction "VCC_2") (pintype "bidirectional"))
      (node (ref "R26") (pin "2") (pinfunction "2_2") (pintype "passive"))
      (node (ref "R27") (pin "2") (pinfunction "2_2") (pintype "passive"))
      (node (ref "R30") (pin "2") (pinfunction "2_2") (pintype "passive"))
      (node (ref "R33") (pin "2") (pinfunction "2_2") (pintype "passive"))
      (node (ref "TLV320AIC1") (pin "12") (pinfunction "AVDD_ADC_12") (pintype "bidirectional"))
      (node (ref "TLV320AIC1") (pin "13") (pinfunction "DRVDD_0_13") (pintype "bidirectional"))
      (node (ref "TLV320AIC1") (pin "18") (pinfunction "DRVDD_1_18") (pintype "bidirectional"))
      (node (ref "TLV320AIC1") (pin "21") (pinfunction "AVDD_DAC_21") (pintype "bidirectional"))
      (node (ref "TLV320AIC1") (pin "40") (pinfunction "IOVDD_40") (pintype "bidirectional"))
      (node (ref "U1") (pin "3") (pinfunction "VDD_3") (pintype "power_in"))
      (node (ref "U2") (pin "3") (pinfunction "VDD_3") (pintype "power_in"))
      (node (ref "U6") (pin "1") (pinfunction "IN_1") (pintype "input"))
      (node (ref "U6") (pin "3") (pinfunction "EN_3") (pintype "input"))
    )
    (net (code "2") (name "+5V") (class "Default")
      (node (ref "AM3352-SOM-EVB-PLATFORM") (pin "3-1") (pinfunction "5.0V_3-1") (pintype "passive"))
      (node (ref "AM3352-SOM-EVB-PLATFORM") (pin "4-1") (pinfunction "5.0V_4-1") (pintype "passive"))
      (node (ref "C18") (pin "1") (pinfunction "1_1") (pintype "passive"))
      (node (ref "C19") (pin "1") (pinfunction "1_1") (pintype "passive"))
      (node (ref "C29") (pin "1") (pinfunction "1_1") (pintype "passive"))
      (node (ref "C30") (pin "1") (pinfunction "1_1") (pintype "passive"))
      (node (ref "C39") (pin "2") (pinfunction "2_2") (pintype "passive"))
      (node (ref "C40") (pin "2") (pinfunction "2_2") (pintype "passive"))
      (node (ref "C53") (pin "1") (pinfunction "1_1") (pintype "passive"))
      (node (ref "C54") (pin "1") (pinfunction "1_1") (pintype "passive"))
      (node (ref "C55") (pin "1") (pinfunction "1_1") (pintype "passive"))
      (node (ref "C56") (pin "1") (pinfunction "1_1") (pintype "passive"))
      (node (ref "C7") (pin "1") (pinfunction "1_1") (pintype "passive"))
      (node (ref "C8") (pin "1") (pinfunction "1_1") (pintype "passive"))
      (node (ref "IC1") (pin "8") (pinfunction "VCC_8") (pintype "power_in"))
      (node (ref "IC2") (pin "8") (pinfunction "VCC_8") (pintype "power_in"))
      (node (ref "L6") (pin "2") (pinfunction "2_2") (pintype "passive"))
      (node (ref "OOBDPICAN") (pin "1") (pinfunction "1_1") (pintype "passive"))
      (node (ref "R37") (pin "2") (pinfunction "2_2") (pintype "passive"))
      (node (ref "R39") (pin "1") (pinfunction "1_1") (pintype "passive"))
      (node (ref "TLV320AIC1") (pin "25") (pinfunction "SPVDD_25") (pintype "bidirectional"))
      (node (ref "U3") (pin "5") (pinfunction "IN_5") (pintype "power_in"))
      (node (ref "U4") (pin "5") (pinfunction "IN_5") (pintype "power_in"))
    )
    (net (code "3") (name "+5V_OTG_PWR") (class "Default")
      (node (ref "C23") (pin "1") (pinfunction "1_1") (pintype "passive"))
      (node (ref "L3") (pin "1") (pinfunction "1_1") (pintype "passive"))
      (node (ref "USB_OTG") (pin "VBUS") (pinfunction "VBUS_VBUS") (pintype "power_in"))
    )
    (net (code "4") (name "+12V") (class "Default")
      (node (ref "C48") (pin "+") (pinfunction "+_+") (pintype "passive"))
      (node (ref "D3") (pin "C") (pinfunction "C_C") (pintype "passive"))
      (node (ref "OOBD2-CONNECTOR") (pin "10") (pinfunction "10_10") (pintype "passive"))
      (node (ref "R32") (pin "1") (pinfunction "1_1") (pintype "passive"))
      (node (ref "U5") (pin "2") (pinfunction "IN_2") (pintype "bidirectional"))
    )
    (net (code "5") (name "3V3") (class "Default")
      (node (ref "AM3352-SOM-EVB-PLATFORM") (pin "3-3") (pinfunction "3.3V_3-3") (pintype "passive"))
      (node (ref "AM3352-SOM-EVB-PLATFORM") (pin "4-3") (pinfunction "3.3V_4-3") (pintype "passive"))
    )
    (net (code "6") (name "AGND") (class "Default")
      (node (ref "C45") (pin "1") (pinfunction "1_1") (pintype "passive"))
      (node (ref "C46") (pin "1") (pinfunction "1_1") (pintype "passive"))
      (node (ref "JP1") (pin "5") (pinfunction "5_5") (pintype "passive"))
      (node (ref "L5") (pin "2") (pinfunction "2_2") (pintype "passive"))
      (node (ref "TLV320AIC1") (pin "11") (pinfunction "AVSS_ADC_11") (pintype "bidirectional"))
      (node (ref "TLV320AIC1") (pin "22") (pinfunction "AVSS_DAC_22") (pintype "bidirectional"))
      (node (ref "TLV320AIC1") (pin "27") (pinfunction "SWINM_27") (pintype "bidirectional"))
      (node (ref "TLV320AIC1") (pin "30") (pinfunction "SWINP_30") (pintype "bidirectional"))
    )
    (net (code "7") (name "AUD_BCLK") (class "Default")
      (node (ref "AM3352-SOM-EVB-PLATFORM") (pin "4-19") (pinfunction "P3_14/SPI1_CLK_4-19") (pintype "passive"))
      (node (ref "TLV320AIC1") (pin "35") (pinfunction "BCLK_35") (pintype "bidirectional"))
    )
    (net (code "8") (name "AUD_DIN") (class "Default")
      (node (ref "AM3352-SOM-EVB-PLATFORM") (pin "4-18") (pinfunction "P3_16/SPI1_D1(MOSI)_4-18") (pintype "passive"))
      (node (ref "TLV320AIC1") (pin "38") (pinfunction "DOUT_38") (pintype "bidirectional"))
    )
    (net (code "9") (name "AUD_DOUT") (class "Default")
      (node (ref "AM3352-SOM-EVB-PLATFORM") (pin "4-20") (pinfunction "P3_17/SPI1_CS0_4-20") (pintype "passive"))
      (node (ref "TLV320AIC1") (pin "37") (pinfunction "DIN_37") (pintype "bidirectional"))
    )
    (net (code "10") (name "AUD_MCLK") (class "Default")
      (node (ref "AM3352-SOM-EVB-PLATFORM") (pin "4-24") (pinfunction "P3_21/LED3_4-24") (pintype "passive"))
      (node (ref "TLV320AIC1") (pin "34") (pinfunction "MCLK_34") (pintype "bidirectional"))
    )
    (net (code "11") (name "AUD_WCLK") (class "Default")
      (node (ref "AM3352-SOM-EVB-PLATFORM") (pin "4-17") (pinfunction "P3_15/SPI1_D0(MISO)_4-17") (pintype "passive"))
      (node (ref "TLV320AIC1") (pin "36") (pinfunction "WCLK_36") (pintype "bidirectional"))
    )
    (net (code "12") (name "DCAN0_RX") (class "Default")
      (node (ref "AM3352-SOM-EVB-PLATFORM") (pin "4-7") (pinfunction "P0_13/I2C2_SCL_4-7") (pintype "passive"))
      (node (ref "IC2") (pin "4") (pinfunction "RXD_4") (pintype "output"))
      (node (ref "U2") (pin "4") (pinfunction "RXD_4") (pintype "output"))
    )
    (net (code "13") (name "DCAN0_TX") (class "Default")
      (node (ref "AM3352-SOM-EVB-PLATFORM") (pin "4-8") (pinfunction "P0_12/I2C2_SDA_4-8") (pintype "passive"))
      (node (ref "IC2") (pin "5") (pinfunction "TXD_5") (pintype "input"))
      (node (ref "U2") (pin "1") (pinfunction "TXD_1") (pintype "input"))
    )
    (net (code "14") (name "DCAN1_RX") (class "Default")
      (node (ref "AM3352-SOM-EVB-PLATFORM") (pin "4-13") (pinfunction "P1_9/UART4_TXD_4-13") (pintype "passive"))
      (node (ref "IC1") (pin "4") (pinfunction "RXD_4") (pintype "output"))
      (node (ref "U1") (pin "4") (pinfunction "RXD_4") (pintype "output"))
    )
    (net (code "15") (name "DCAN1_TX") (class "Default")
      (node (ref "AM3352-SOM-EVB-PLATFORM") (pin "4-14") (pinfunction "P1_8/UART4_RXD_4-14") (pintype "passive"))
      (node (ref "IC1") (pin "5") (pinfunction "TXD_5") (pintype "input"))
      (node (ref "U1") (pin "1") (pinfunction "TXD_1") (pintype "input"))
    )
    (net (code "16") (name "DVDD") (class "Default")
      (node (ref "C37") (pin "2") (pinfunction "2_2") (pintype "passive"))
      (node (ref "C38") (pin "2") (pinfunction "2_2") (pintype "passive"))
      (node (ref "C59") (pin "2") (pinfunction "2_2") (pintype "passive"))
      (node (ref "TLV320AIC1") (pin "33") (pinfunction "DVDD_33") (pintype "bidirectional"))
      (node (ref "U6") (pin "5") (pinfunction "OUT_5") (pintype "passive"))
    )
    (net (code "17") (name "EXT_WAKEUP") (class "Default")
      (node (ref "AM3352-SOM-EVB-PLATFORM") (pin "3-20") (pinfunction "EXT_WAKEUP_3-20") (pintype "passive"))
      (node (ref "R34") (pin "1") (pinfunction "1_1") (pintype "passive"))
    )
    (net (code "18") (name "GND") (class "Default")
      (node (ref "AM3352-SOM-EVB-PLATFORM") (pin "3-2") (pinfunction "GND_3-2") (pintype "passive"))
      (node (ref "AM3352-SOM-EVB-PLATFORM") (pin "3-4") (pinfunction "GND_3-4") (pintype "passive"))
      (node (ref "AM3352-SOM-EVB-PLATFORM") (pin "4-2") (pinfunction "GND_4-2") (pintype "passive"))
      (node (ref "AM3352-SOM-EVB-PLATFORM") (pin "4-4") (pinfunction "GND_4-4") (pintype "passive"))
      (node (ref "AM3352-SOM-EVB-PLATFORM") (pin "4-40") (pinfunction "GNDA_4-40") (pintype "passive"))
      (node (ref "BAT1") (pin "GND") (pinfunction "-_GND") (pintype "power_in"))
      (node (ref "C10") (pin "2") (pinfunction "2_2") (pintype "passive"))
      (node (ref "C11") (pin "2") (pinfunction "2_2") (pintype "passive"))
      (node (ref "C17") (pin "2") (pinfunction "2_2") (pintype "passive"))
      (node (ref "C18") (pin "2") (pinfunction "2_2") (pintype "passive"))
      (node (ref "C19") (pin "2") (pinfunction "2_2") (pintype "passive"))
      (node (ref "C20") (pin "2") (pinfunction "2_2") (pintype "passive"))
      (node (ref "C21") (pin "2") (pinfunction "2_2") (pintype "passive"))
      (node (ref "C22") (pin "2") (pinfunction "2_2") (pintype "passive"))
      (node (ref "C23") (pin "2") (pinfunction "2_2") (pintype "passive"))
      (node (ref "C24") (pin "2") (pinfunction "2_2") (pintype "passive"))
      (node (ref "C25") (pin "2") (pinfunction "2_2") (pintype "passive"))
      (node (ref "C26") (pin "2") (pinfunction "2_2") (pintype "passive"))
      (node (ref "C27") (pin "2") (pinfunction "2_2") (pintype "passive"))
      (node (ref "C28") (pin "2") (pinfunction "2_2") (pintype "passive"))
      (node (ref "C29") (pin "2") (pinfunction "2_2") (pintype "passive"))
      (node (ref "C30") (pin "2") (pinfunction "2_2") (pintype "passive"))
      (node (ref "C31") (pin "1") (pinfunction "1_1") (pintype "passive"))
      (node (ref "C32") (pin "1") (pinfunction "1_1") (pintype "passive"))
      (node (ref "C33") (pin "1") (pinfunction "1_1") (pintype "passive"))
      (node (ref "C34") (pin "1") (pinfunction "1_1") (pintype "passive"))
      (node (ref "C35") (pin "1") (pinfunction "1_1") (pintype "passive"))
      (node (ref "C36") (pin "1") (pinfunction "1_1") (pintype "passive"))
      (node (ref "C37") (pin "1") (pinfunction "1_1") (pintype "passive"))
      (node (ref "C38") (pin "1") (pinfunction "1_1") (pintype "passive"))
      (node (ref "C39") (pin "1") (pinfunction "1_1") (pintype "passive"))
      (node (ref "C40") (pin "1") (pinfunction "1_1") (pintype "passive"))
      (node (ref "C41") (pin "2") (pinfunction "2_2") (pintype "passive"))
      (node (ref "C42") (pin "2") (pinfunction "2_2") (pintype "passive"))
      (node (ref "C43") (pin "2") (pinfunction "2_2") (pintype "passive"))
      (node (ref "C44") (pin "2") (pinfunction "2_2") (pintype "passive"))
      (node (ref "C47") (pin "1") (pinfunction "1_1") (pintype "passive"))
      (node (ref "C48") (pin "-") (pinfunction "-_-") (pintype "passive"))
      (node (ref "C49") (pin "2") (pinfunction "2_2") (pintype "passive"))
      (node (ref "C50") (pin "2") (pinfunction "2_2") (pintype "passive"))
      (node (ref "C53") (pin "2") (pinfunction "2_2") (pintype "passive"))
      (node (ref "C54") (pin "2") (pinfunction "2_2") (pintype "passive"))
      (node (ref "C55") (pin "2") (pinfunction "2_2") (pintype "passive"))
      (node (ref "C56") (pin "2") (pinfunction "2_2") (pintype "passive"))
      (node (ref "C57") (pin "1") (pinfunction "1_1") (pintype "passive"))
      (node (ref "C58") (pin "1") (pinfunction "1_1") (pintype "passive"))
      (node (ref "C59") (pin "1") (pinfunction "1_1") (pintype "passive"))
      (node (ref "C6") (pin "2") (pinfunction "2_2") (pintype "passive"))
      (node (ref "C7") (pin "2") (pinfunction "2_2") (pintype "passive"))
      (node (ref "C8") (pin "2") (pinfunction "2_2") (pintype "passive"))
      (node (ref "C9") (pin "2") (pinfunction "2_2") (pintype "passive"))
      (node (ref "D3") (pin "A") (pinfunction "A_A") (pintype "passive"))
      (node (ref "IC1") (pin "1") (pinfunction "GND1_1") (pintype "power_in"))
      (node (ref "IC1") (pin "10") (pinfunction "GND1_10") (pintype "power_in"))
      (node (ref "IC1") (pin "3") (pinfunction "GND1_3") (pintype "power_in"))
      (node (ref "IC1") (pin "7") (pinfunction "GND1_7") (pintype "power_in"))
      (node (ref "IC1") (pin "9") (pinfunction "GND1_9") (pintype "power_in"))
      (node (ref "IC2") (pin "1") (pinfunction "GND1_1") (pintype "power_in"))
      (node (ref "IC2") (pin "10") (pinfunction "GND1_10") (pintype "power_in"))
      (node (ref "IC2") (pin "3") (pinfunction "GND1_3") (pintype "power_in"))
      (node (ref "IC2") (pin "7") (pinfunction "GND1_7") (pintype "power_in"))
      (node (ref "IC2") (pin "9") (pinfunction "GND1_9") (pintype "power_in"))
      (node (ref "IC3") (pin "10") (pinfunction "NC_10") (pintype "bidirectional"))
      (node (ref "IC3") (pin "11") (pinfunction "NC_11") (pintype "bidirectional"))
      (node (ref "IC3") (pin "12") (pinfunction "NC_12") (pintype "bidirectional"))
      (node (ref "IC3") (pin "13") (pinfunction "GND_13") (pintype "bidirectional"))
      (node (ref "IC3") (pin "5") (pinfunction "NC_5") (pintype "bidirectional"))
      (node (ref "IC3") (pin "6") (pinfunction "NC_6") (pintype "bidirectional"))
      (node (ref "IC3") (pin "7") (pinfunction "NC_7") (pintype "bidirectional"))
      (node (ref "IC3") (pin "8") (pinfunction "NC_8") (pintype "bidirectional"))
      (node (ref "IC3") (pin "9") (pinfunction "NC_9") (pintype "bidirectional"))
      (node (ref "JP1") (pin "6") (pinfunction "6_6") (pintype "passive"))
      (node (ref "L1") (pin "1") (pinfunction "1_1") (pintype "passive"))
      (node (ref "L2") (pin "1") (pinfunction "1_1") (pintype "passive"))
      (node (ref "L5") (pin "1") (pinfunction "1_1") (pintype "passive"))
      (node (ref "LED1") (pin "C") (pinfunction "C_C") (pintype "passive"))
      (node (ref "LED2") (pin "C") (pinfunction "C_C") (pintype "passive"))
      (node (ref "OOBD2-CONNECTOR") (pin "3") (pinfunction "3_3") (pintype "passive"))
      (node (ref "OOBDPICAN") (pin "5") (pinfunction "5_5") (pintype "passive"))
      (node (ref "PWR_LED") (pin "C") (pinfunction "C_C") (pintype "passive"))
      (node (ref "R12") (pin "2") (pinfunction "2_2") (pintype "passive"))
      (node (ref "R15") (pin "1") (pinfunction "1_1") (pintype "passive"))
      (node (ref "R16") (pin "1") (pinfunction "1_1") (pintype "passive"))
      (node (ref "R17") (pin "1") (pinfunction "1_1") (pintype "passive"))
      (node (ref "R18") (pin "1") (pinfunction "1_1") (pintype "passive"))
      (node (ref "R19") (pin "1") (pinfunction "1_1") (pintype "passive"))
      (node (ref "R31") (pin "2") (pinfunction "2_2") (pintype "passive"))
      (node (ref "R35") (pin "2") (pinfunction "2_2") (pintype "passive"))
      (node (ref "R36") (pin "2") (pinfunction "2_2") (pintype "passive"))
      (node (ref "R41") (pin "1") (pinfunction "1_1") (pintype "passive"))
      (node (ref "R5") (pin "2") (pinfunction "2_2") (pintype "passive"))
      (node (ref "TLV320AIC1") (pin "16") (pinfunction "DRVSS_16") (pintype "bidirectional"))
      (node (ref "TLV320AIC1") (pin "24") (pinfunction "SPVSS_24") (pintype "bidirectional"))
      (node (ref "TLV320AIC1") (pin "39") (pinfunction "DVSS_39") (pintype "bidirectional"))
      (node (ref "U1") (pin "2") (pinfunction "VSS_2") (pintype "power_in"))
      (node (ref "U2") (pin "2") (pinfunction "VSS_2") (pintype "power_in"))
      (node (ref "U3") (pin "2") (pinfunction "GND_2") (pintype "power_in"))
      (node (ref "U4") (pin "2") (pinfunction "GND_2") (pintype "power_in"))
      (node (ref "U5") (pin "4") (pinfunction "GND_4") (pintype "bidirectional"))
      (node (ref "U6") (pin "2") (pinfunction "GND_2") (pintype "input"))
      (node (ref "USB_HOST") (pin "4") (pinfunction "4_4") (pintype "passive"))
      (node (ref "USB_OTG") (pin "GND") (pinfunction "GND_GND") (pintype "power_in"))
    )
    (net (code "19") (name "GNDA") (class "Default")
      (node (ref "C1") (pin "2") (pinfunction "2_2") (pintype "passive"))
      (node (ref "C12") (pin "2") (pinfunction "2_2") (pintype "passive"))
      (node (ref "C13") (pin "2") (pinfunction "2_2") (pintype "passive"))
      (node (ref "C14") (pin "2") (pinfunction "2_2") (pintype "passive"))
      (node (ref "C15") (pin "2") (pinfunction "2_2") (pintype "passive"))
      (node (ref "C16") (pin "2") (pinfunction "2_2") (pintype "passive"))
      (node (ref "C17") (pin "1") (pinfunction "1_1") (pintype "passive"))
      (node (ref "C2") (pin "2") (pinfunction "2_2") (pintype "passive"))
      (node (ref "C3") (pin "2") (pinfunction "2_2") (pintype "passive"))
      (node (ref "C4") (pin "2") (pinfunction "2_2") (pintype "passive"))
      (node (ref "C5") (pin "2") (pinfunction "2_2") (pintype "passive"))
      (node (ref "C6") (pin "1") (pinfunction "1_1") (pintype "passive"))
      (node (ref "D1") (pin "3") (pinfunction "CC_3") (pintype "bidirectional"))
      (node (ref "D2") (pin "3") (pinfunction "CC_3") (pintype "bidirectional"))
      (node (ref "IC1") (pin "11") (pinfunction "GND2_11") (pintype "power_in"))
      (node (ref "IC1") (pin "13") (pinfunction "GND2_13") (pintype "power_in"))
      (node (ref "IC1") (pin "16") (pinfunction "GND2_16") (pintype "power_in"))
      (node (ref "IC1") (pin "20") (pinfunction "GND2_20") (pintype "power_in"))
      (node (ref "IC2") (pin "11") (pinfunction "GND2_11") (pintype "power_in"))
      (node (ref "IC2") (pin "13") (pinfunction "GND2_13") (pintype "power_in"))
      (node (ref "IC2") (pin "16") (pinfunction "GND2_16") (pintype "power_in"))
      (node (ref "IC2") (pin "20") (pinfunction "GND2_20") (pintype "power_in"))
      (node (ref "R1") (pin "1") (pinfunction "1_1") (pintype "passive"))
      (node (ref "R41") (pin "2") (pinfunction "2_2") (pintype "passive"))
      (node (ref "R8") (pin "1") (pinfunction "1_1") (pintype "passive"))
    )
    (net (code "20") (name "HS-CAN_H") (class "Default")
      (node (ref "D1") (pin "2") (pinfunction "C2_2") (pintype "bidirectional"))
      (node (ref "IC1") (pin "17") (pinfunction "CAN_H_17") (pintype "bidirectional"))
      (node (ref "OOBD2-CONNECTOR") (pin "7") (pinfunction "7_7") (pintype "passive"))
      (node (ref "R2") (pin "2") (pinfunction "2_2") (pintype "passive"))
      (node (ref "R6") (pin "2") (pinfunction "2_2") (pintype "passive"))
    )
    (net (code "21") (name "HS-CAN_L") (class "Default")
      (node (ref "D1") (pin "1") (pinfunction "C1_1") (pintype "bidirectional"))
      (node (ref "HS-CAN") (pin "1") (pinfunction "1_1") (pintype "passive"))
      (node (ref "IC1") (pin "15") (pinfunction "CAN_L_15") (pintype "bidirectional"))
      (node (ref "OOBD2-CONNECTOR") (pin "6") (pinfunction "6_6") (pintype "passive"))
      (node (ref "R7") (pin "1") (pinfunction "1_1") (pintype "passive"))
    )
    (net (code "22") (name "HS-CAN_RS") (class "Default")
      (node (ref "AM3352-SOM-EVB-PLATFORM") (pin "4-26") (pinfunction "P3_8/EMU1_4-26") (pintype "passive"))
      (node (ref "R4") (pin "2") (pinfunction "2_2") (pintype "passive"))
    )
    (net (code "23") (name "I2C0-SCL") (class "Default")
      (node (ref "AM3352-SOM-EVB-PLATFORM") (pin "4-15") (pinfunction "P3_6/I2C0-SCL_4-15") (pintype "passive"))
      (node (ref "IC3") (pin "16") (pinfunction "SCL_16") (pintype "bidirectional"))
      (node (ref "R26") (pin "1") (pinfunction "1_1") (pintype "passive"))
      (node (ref "TLV320AIC1") (pin "1") (pinfunction "SCL_1") (pintype "bidirectional"))
    )
    (net (code "24") (name "I2C0-SDA") (class "Default")
      (node (ref "AM3352-SOM-EVB-PLATFORM") (pin "4-16") (pinfunction "P3_5/I2C0-SDA_4-16") (pintype "passive"))
      (node (ref "IC3") (pin "15") (pinfunction "SDA_15") (pintype "bidirectional"))
      (node (ref "R27") (pin "1") (pinfunction "1_1") (pintype "passive"))
      (node (ref "TLV320AIC1") (pin "2") (pinfunction "SDA_2") (pintype "bidirectional"))
    )
    (net (code "25") (name "LED1") (class "Default")
      (node (ref "AM3352-SOM-EVB-PLATFORM") (pin "4-21") (pinfunction "P3_18/LED1_4-21") (pintype "passive"))
      (node (ref "R38") (pin "1") (pinfunction "1_1") (pintype "passive"))
    )
    (net (code "26") (name "LED2") (class "Default")
      (node (ref "AM3352-SOM-EVB-PLATFORM") (pin "4-23") (pinfunction "P3_20/LED2_4-23") (pintype "passive"))
      (node (ref "R40") (pin "1") (pinfunction "1_1") (pintype "passive"))
    )
    (net (code "27") (name "MS-CAN_H") (class "Default")
      (node (ref "D2") (pin "2") (pinfunction "C2_2") (pintype "bidirectional"))
      (node (ref "IC2") (pin "17") (pinfunction "CAN_H_17") (pintype "bidirectional"))
      (node (ref "OOBD2-CONNECTOR") (pin "1") (pinfunction "1_1") (pintype "passive"))
      (node (ref "R13") (pin "1") (pinfunction "1_1") (pintype "passive"))
      (node (ref "R9") (pin "2") (pinfunction "2_2") (pintype "passive"))
    )
    (net (code "28") (name "MS-CAN_L") (class "Default")
      (node (ref "D2") (pin "1") (pinfunction "C1_1") (pintype "bidirectional"))
      (node (ref "IC2") (pin "15") (pinfunction "CAN_L_15") (pintype "bidirectional"))
      (node (ref "MS-CAN") (pin "1") (pinfunction "1_1") (pintype "passive"))
      (node (ref "OOBD2-CONNECTOR") (pin "2") (pinfunction "2_2") (pintype "passive"))
      (node (ref "R14") (pin "1") (pinfunction "1_1") (pintype "passive"))
    )
    (net (code "29") (name "MS-CAN_RS") (class "Default")
      (node (ref "AM3352-SOM-EVB-PLATFORM") (pin "4-25") (pinfunction "P3_7/EMU0_4-25") (pintype "passive"))
      (node (ref "R11") (pin "2") (pinfunction "2_2") (pintype "passive"))
    )
    (net (code "30") (name "Net-(BAT1-+)") (class "Default")
      (node (ref "BAT1") (pin "VCC@1") (pinfunction "+_VCC@1") (pintype "power_in"))
      (node (ref "IC3") (pin "14") (pinfunction "VBAT_14") (pintype "bidirectional"))
    )
    (net (code "31") (name "Net-(C3-Pad1)") (class "Default")
      (node (ref "C3") (pin "1") (pinfunction "1_1") (pintype "passive"))
      (node (ref "R2") (pin "1") (pinfunction "1_1") (pintype "passive"))
      (node (ref "R3") (pin "1") (pinfunction "1_1") (pintype "passive"))
    )
    (net (code "32") (name "Net-(C14-Pad1)") (class "Default")
      (node (ref "C14") (pin "1") (pinfunction "1_1") (pintype "passive"))
      (node (ref "R10") (pin "1") (pinfunction "1_1") (pintype "passive"))
      (node (ref "R9") (pin "1") (pinfunction "1_1") (pintype "passive"))
    )
    (net (code "33") (name "Net-(C24-Pad1)") (class "Default")
      (node (ref "C24") (pin "1") (pinfunction "1_1") (pintype "passive"))
      (node (ref "L4") (pin "2") (pinfunction "2_2") (pintype "passive"))
      (node (ref "USB_HOST") (pin "1") (pinfunction "1_1") (pintype "passive"))
    )
    (net (code "34") (name "Net-(C45-Pad2)") (class "Default")
      (node (ref "C45") (pin "2") (pinfunction "2_2") (pintype "passive"))
      (node (ref "JP1") (pin "4") (pinfunction "4_4") (pintype "passive"))
      (node (ref "R29") (pin "2") (pinfunction "2_2") (pintype "passive"))
    )
    (net (code "35") (name "Net-(C46-Pad2)") (class "Default")
      (node (ref "C46") (pin "2") (pinfunction "2_2") (pintype "passive"))
      (node (ref "JP1") (pin "2") (pinfunction "2_2") (pintype "passive"))
      (node (ref "R28") (pin "2") (pinfunction "2_2") (pintype "passive"))
    )
    (net (code "36") (name "Net-(C49-Pad1)") (class "Default")
      (node (ref "C49") (pin "1") (pinfunction "1_1") (pintype "passive"))
      (node (ref "R31") (pin "1") (pinfunction "1_1") (pintype "passive"))
      (node (ref "R34") (pin "2") (pinfunction "2_2") (pintype "passive"))
      (node (ref "WAKE-UP") (pin "2") (pinfunction "2_2") (pintype "passive"))
    )
    (net (code "37") (name "Net-(C52-Pad2)") (class "Default")
      (node (ref "C52") (pin "2") (pinfunction "2_2") (pintype "passive"))
      (node (ref "R35") (pin "1") (pinfunction "1_1") (pintype "passive"))
    )
    (net (code "38") (name "Net-(HS-CAN-Pad2)") (class "Default")
      (node (ref "HS-CAN") (pin "2") (pinfunction "2_2") (pintype "passive"))
      (node (ref "R3") (pin "2") (pinfunction "2_2") (pintype "passive"))
    )
    (net (code "39") (name "Net-(IC1-R_S)") (class "Default")
      (node (ref "IC1") (pin "18") (pinfunction "R_S_18") (pintype "passive"))
      (node (ref "R1") (pin "2") (pinfunction "2_2") (pintype "passive"))
    )
    (net (code "40") (name "Net-(IC1-V_ISOIN)") (class "Default")
      (node (ref "C1") (pin "1") (pinfunction "1_1") (pintype "passive"))
      (node (ref "C2") (pin "1") (pinfunction "1_1") (pintype "passive"))
      (node (ref "C4") (pin "1") (pinfunction "1_1") (pintype "passive"))
      (node (ref "C5") (pin "1") (pinfunction "1_1") (pintype "passive"))
      (node (ref "IC1") (pin "12") (pinfunction "V_ISOOUT_12") (pintype "output"))
      (node (ref "IC1") (pin "19") (pinfunction "V_ISOIN_19") (pintype "input"))
    )
    (net (code "41") (name "Net-(IC2-R_S)") (class "Default")
      (node (ref "IC2") (pin "18") (pinfunction "R_S_18") (pintype "passive"))
      (node (ref "R8") (pin "2") (pinfunction "2_2") (pintype "passive"))
    )
    (net (code "42") (name "Net-(IC2-V_ISOIN)") (class "Default")
      (node (ref "C12") (pin "1") (pinfunction "1_1") (pintype "passive"))
      (node (ref "C13") (pin "1") (pinfunction "1_1") (pintype "passive"))
      (node (ref "C15") (pin "1") (pinfunction "1_1") (pintype "passive"))
      (node (ref "C16") (pin "1") (pinfunction "1_1") (pintype "passive"))
      (node (ref "IC2") (pin "12") (pinfunction "V_ISOOUT_12") (pintype "output"))
      (node (ref "IC2") (pin "19") (pinfunction "V_ISOIN_19") (pintype "input"))
    )
    (net (code "43") (name "Net-(IC3-~{INT})") (class "Default")
      (node (ref "IC3") (pin "3") (pinfunction "~{INT}_3") (pintype "bidirectional"))
      (node (ref "R33") (pin "1") (pinfunction "1_1") (pintype "passive"))
    )
    (net (code "44") (name "Net-(L1-Pad2)") (class "Default")
      (node (ref "L1") (pin "2") (pinfunction "2_2") (pintype "passive"))
      (node (ref "USB_OTG") (pin "GND1") (pinfunction "GND1_GND1") (pintype "input"))
      (node (ref "USB_OTG") (pin "GND2") (pinfunction "GND2_GND2") (pintype "input"))
      (node (ref "USB_OTG") (pin "GND3") (pinfunction "GND3_GND3") (pintype "input"))
      (node (ref "USB_OTG") (pin "GND4") (pinfunction "GND4_GND4") (pintype "input"))
    )
    (net (code "45") (name "Net-(LED1-PadA)") (class "Default")
      (node (ref "LED1") (pin "A") (pinfunction "A_A") (pintype "passive"))
      (node (ref "R38") (pin "2") (pinfunction "2_2") (pintype "passive"))
    )
    (net (code "46") (name "Net-(LED2-PadA)") (class "Default")
      (node (ref "LED2") (pin "A") (pinfunction "A_A") (pintype "passive"))
      (node (ref "R40") (pin "2") (pinfunction "2_2") (pintype "passive"))
    )
    (net (code "47") (name "Net-(MS-CAN-Pad2)") (class "Default")
      (node (ref "MS-CAN") (pin "2") (pinfunction "2_2") (pintype "passive"))
      (node (ref "R10") (pin "2") (pinfunction "2_2") (pintype "passive"))
    )
    (net (code "48") (name "Net-(PWR_LED-PadA)") (class "Default")
      (node (ref "PWR_LED") (pin "A") (pinfunction "A_A") (pintype "passive"))
      (node (ref "R39") (pin "2") (pinfunction "2_2") (pintype "passive"))
    )
    (net (code "49") (name "Net-(R30-Pad1)") (class "Default")
      (node (ref "R30") (pin "1") (pinfunction "1_1") (pintype "passive"))
      (node (ref "WAKE-UP") (pin "1") (pinfunction "1_1") (pintype "passive"))
    )
    (net (code "50") (name "Net-(TLV320AIC1-LEFT_LOP)") (class "Default")
      (node (ref "JP1") (pin "3") (pinfunction "3_3") (pintype "passive"))
      (node (ref "TLV320AIC1") (pin "19") (pinfunction "LEFT_LOP_19") (pintype "bidirectional"))
    )
    (net (code "51") (name "Net-(TLV320AIC1-RIGHT_LOP)") (class "Default")
      (node (ref "JP1") (pin "1") (pinfunction "1_1") (pintype "passive"))
      (node (ref "TLV320AIC1") (pin "20") (pinfunction "RIGHT_LOP_20") (pintype "bidirectional"))
    )
    (net (code "52") (name "Net-(TLV320AIC1-SPOM)") (class "Default")
      (node (ref "R29") (pin "1") (pinfunction "1_1") (pintype "passive"))
      (node (ref "TLV320AIC1") (pin "23") (pinfunction "SPOM_23") (pintype "bidirectional"))
    )
    (net (code "53") (name "Net-(TLV320AIC1-SPOP)") (class "Default")
      (node (ref "R28") (pin "1") (pinfunction "1_1") (pintype "passive"))
      (node (ref "TLV320AIC1") (pin "26") (pinfunction "SPOP_26") (pintype "bidirectional"))
    )
    (net (code "54") (name "Net-(U1-CANH)") (class "Default")
      (node (ref "R6") (pin "1") (pinfunction "1_1") (pintype "passive"))
      (node (ref "U1") (pin "7") (pinfunction "CANH_7") (pintype "output"))
    )
    (net (code "55") (name "Net-(U1-CANL)") (class "Default")
      (node (ref "R7") (pin "2") (pinfunction "2_2") (pintype "passive"))
      (node (ref "U1") (pin "6") (pinfunction "CANL_6") (pintype "output"))
    )
    (net (code "56") (name "Net-(U1-RS)") (class "Default")
      (node (ref "R4") (pin "1") (pinfunction "1_1") (pintype "passive"))
      (node (ref "R5") (pin "1") (pinfunction "1_1") (pintype "passive"))
      (node (ref "U1") (pin "8") (pinfunction "RS_8") (pintype "input"))
    )
    (net (code "57") (name "Net-(U2-CANH)") (class "Default")
      (node (ref "R13") (pin "2") (pinfunction "2_2") (pintype "passive"))
      (node (ref "U2") (pin "7") (pinfunction "CANH_7") (pintype "output"))
    )
    (net (code "58") (name "Net-(U2-CANL)") (class "Default")
      (node (ref "R14") (pin "2") (pinfunction "2_2") (pintype "passive"))
      (node (ref "U2") (pin "6") (pinfunction "CANL_6") (pintype "output"))
    )
    (net (code "59") (name "Net-(U2-RS)") (class "Default")
      (node (ref "R11") (pin "1") (pinfunction "1_1") (pintype "passive"))
      (node (ref "R12") (pin "1") (pinfunction "1_1") (pintype "passive"))
      (node (ref "U2") (pin "8") (pinfunction "RS_8") (pintype "input"))
    )
    (net (code "60") (name "Net-(U3-EN)") (class "Default")
      (node (ref "R17") (pin "2") (pinfunction "2_2") (pintype "passive"))
      (node (ref "R21") (pin "1") (pinfunction "1_1") (pintype "passive"))
      (node (ref "R22") (pin "1") (pinfunction "1_1") (pintype "passive"))
      (node (ref "U3") (pin "4") (pinfunction "EN_4") (pintype "bidirectional"))
    )
    (net (code "61") (name "Net-(U3-ISET)") (class "Default")
      (node (ref "R15") (pin "2") (pinfunction "2_2") (pintype "passive"))
      (node (ref "U3") (pin "3") (pinfunction "ISET_3") (pintype "bidirectional"))
    )
    (net (code "62") (name "Net-(U3-OUT)") (class "Default")
      (node (ref "C25") (pin "1") (pinfunction "1_1") (pintype "passive"))
      (node (ref "C27") (pin "1") (pinfunction "1_1") (pintype "passive"))
      (node (ref "L3") (pin "2") (pinfunction "2_2") (pintype "passive"))
      (node (ref "R20") (pin "2") (pinfunction "2_2") (pintype "passive"))
      (node (ref "U3") (pin "1") (pinfunction "OUT_1") (pintype "bidirectional"))
    )
    (net (code "63") (name "Net-(U4-EN)") (class "Default")
      (node (ref "R18") (pin "2") (pinfunction "2_2") (pintype "passive"))
      (node (ref "R24") (pin "1") (pinfunction "1_1") (pintype "passive"))
      (node (ref "R25") (pin "1") (pinfunction "1_1") (pintype "passive"))
      (node (ref "U4") (pin "4") (pinfunction "EN_4") (pintype "bidirectional"))
    )
    (net (code "64") (name "Net-(U4-ISET)") (class "Default")
      (node (ref "R16") (pin "2") (pinfunction "2_2") (pintype "passive"))
      (node (ref "U4") (pin "3") (pinfunction "ISET_3") (pintype "bidirectional"))
    )
    (net (code "65") (name "Net-(U4-OUT)") (class "Default")
      (node (ref "C26") (pin "1") (pinfunction "1_1") (pintype "passive"))
      (node (ref "C28") (pin "1") (pinfunction "1_1") (pintype "passive"))
      (node (ref "L4") (pin "1") (pinfunction "1_1") (pintype "passive"))
      (node (ref "R23") (pin "2") (pinfunction "2_2") (pintype "passive"))
      (node (ref "U4") (pin "1") (pinfunction "OUT_1") (pintype "bidirectional"))
    )
    (net (code "66") (name "Net-(U5-BS)") (class "Default")
      (node (ref "C51") (pin "1") (pinfunction "1_1") (pintype "passive"))
      (node (ref "U5") (pin "1") (pinfunction "BS_1") (pintype "bidirectional"))
    )
    (net (code "67") (name "Net-(U5-COMP)") (class "Default")
      (node (ref "C52") (pin "1") (pinfunction "1_1") (pintype "passive"))
      (node (ref "U5") (pin "6") (pinfunction "COMP_6") (pintype "bidirectional"))
    )
    (net (code "68") (name "Net-(U5-EN)") (class "Default")
      (node (ref "R32") (pin "2") (pinfunction "2_2") (pintype "passive"))
      (node (ref "U5") (pin "7") (pinfunction "EN_7") (pintype "bidirectional"))
    )
    (net (code "69") (name "Net-(U5-FB)") (class "Default")
      (node (ref "R36") (pin "1") (pinfunction "1_1") (pintype "passive"))
      (node (ref "R37") (pin "1") (pinfunction "1_1") (pintype "passive"))
      (node (ref "U5") (pin "5") (pinfunction "FB_5") (pintype "bidirectional"))
    )
    (net (code "70") (name "Net-(U5-SS)") (class "Default")
      (node (ref "C50") (pin "1") (pinfunction "1_1") (pintype "passive"))
      (node (ref "U5") (pin "8") (pinfunction "SS_8") (pintype "bidirectional"))
    )
    (net (code "71") (name "Net-(U5-SW)") (class "Default")
      (node (ref "C51") (pin "2") (pinfunction "2_2") (pintype "passive"))
      (node (ref "L6") (pin "1") (pinfunction "1_1") (pintype "passive"))
      (node (ref "U5") (pin "3") (pinfunction "SW_3") (pintype "bidirectional"))
    )
    (net (code "72") (name "Net-(U6-BP)") (class "Default")
      (node (ref "C58") (pin "2") (pinfunction "2_2") (pintype "passive"))
      (node (ref "U6") (pin "4") (pinfunction "BP_4") (pintype "input"))
    )
    (net (code "73") (name "Net-(USB_HOST-5)") (class "Default")
      (node (ref "L2") (pin "2") (pinfunction "2_2") (pintype "passive"))
      (node (ref "USB_HOST") (pin "P$1") (pinfunction "5_P$1") (pintype "input"))
      (node (ref "USB_HOST") (pin "P$2") (pinfunction "6_P$2") (pintype "input"))
    )
    (net (code "74") (name "SYS_RESETN") (class "Default")
      (node (ref "AM3352-SOM-EVB-PLATFORM") (pin "4-28") (pinfunction "SYS_RESETN_4-28") (pintype "passive"))
      (node (ref "IC3") (pin "4") (pinfunction "~{RST}_4") (pintype "bidirectional"))
      (node (ref "TLV320AIC1") (pin "31") (pinfunction "RESETN_31") (pintype "bidirectional"))
    )
    (net (code "75") (name "USB0_CE") (class "Default")
      (node (ref "AM3352-SOM-EVB-PLATFORM") (pin "3-14") (pinfunction "USB0_CE_3-14") (pintype "passive"))
      (node (ref "R21") (pin "2") (pinfunction "2_2") (pintype "passive"))
    )
    (net (code "76") (name "USB0_DM") (class "Default")
      (node (ref "AM3352-SOM-EVB-PLATFORM") (pin "3-15") (pinfunction "USB0_DM_3-15") (pintype "passive"))
      (node (ref "USB_OTG") (pin "D-") (pinfunction "D-_D-") (pintype "input"))
    )
    (net (code "77") (name "USB0_DP") (class "Default")
      (node (ref "AM3352-SOM-EVB-PLATFORM") (pin "3-13") (pinfunction "USB0_DP_3-13") (pintype "passive"))
      (node (ref "USB_OTG") (pin "D+") (pinfunction "D+_D+") (pintype "input"))
    )
    (net (code "78") (name "USB0_DRV") (class "Default")
      (node (ref "AM3352-SOM-EVB-PLATFORM") (pin "3-16") (pinfunction "USB0-DRV_3-16") (pintype "passive"))
      (node (ref "R22") (pin "2") (pinfunction "2_2") (pintype "passive"))
    )
    (net (code "79") (name "USB0_ID") (class "Default")
      (node (ref "AM3352-SOM-EVB-PLATFORM") (pin "3-12") (pinfunction "USB0-ID_3-12") (pintype "passive"))
      (node (ref "USB_OTG") (pin "ID") (pinfunction "ID_ID") (pintype "input"))
    )
    (net (code "80") (name "USB0_VBUS") (class "Default")
      (node (ref "AM3352-SOM-EVB-PLATFORM") (pin "3-11") (pinfunction "USB0-VBUS_3-11") (pintype "passive"))
      (node (ref "R20") (pin "1") (pinfunction "1_1") (pintype "passive"))
    )
    (net (code "81") (name "USB1_CE") (class "Default")
      (node (ref "AM3352-SOM-EVB-PLATFORM") (pin "3-8") (pinfunction "USB1_CE_3-8") (pintype "passive"))
      (node (ref "R24") (pin "2") (pinfunction "2_2") (pintype "passive"))
    )
    (net (code "82") (name "USB1_DM") (class "Default")
      (node (ref "AM3352-SOM-EVB-PLATFORM") (pin "3-9") (pinfunction "USB1_DM_3-9") (pintype "passive"))
      (node (ref "OOBDPICAN") (pin "2") (pinfunction "2_2") (pintype "passive"))
      (node (ref "USB_HOST") (pin "2") (pinfunction "2_2") (pintype "passive"))
    )
    (net (code "83") (name "USB1_DP") (class "Default")
      (node (ref "AM3352-SOM-EVB-PLATFORM") (pin "3-7") (pinfunction "USB1_DP_3-7") (pintype "passive"))
      (node (ref "OOBDPICAN") (pin "4") (pinfunction "4_4") (pintype "passive"))
      (node (ref "USB_HOST") (pin "3") (pinfunction "3_3") (pintype "passive"))
    )
    (net (code "84") (name "USB1_DRV") (class "Default")
      (node (ref "AM3352-SOM-EVB-PLATFORM") (pin "3-10") (pinfunction "USB1_DRV_3-10") (pintype "passive"))
      (node (ref "R25") (pin "2") (pinfunction "2_2") (pintype "passive"))
    )
    (net (code "85") (name "USB1_ID") (class "Default")
      (node (ref "AM3352-SOM-EVB-PLATFORM") (pin "3-6") (pinfunction "USB1_ID_3-6") (pintype "passive"))
      (node (ref "R19") (pin "2") (pinfunction "2_2") (pintype "passive"))
    )
    (net (code "86") (name "USB1_VBUS") (class "Default")
      (node (ref "AM3352-SOM-EVB-PLATFORM") (pin "3-5") (pinfunction "USB1-VBUS_3-5") (pintype "passive"))
      (node (ref "R23") (pin "1") (pinfunction "1_1") (pintype "passive"))
    )
    (net (code "87") (name "unconnected-(AM3352-SOM-EVB-PLATFORM-AIN4-Pad4-35)") (class "Default")
      (node (ref "AM3352-SOM-EVB-PLATFORM") (pin "4-35") (pinfunction "AIN4_4-35") (pintype "passive"))
    )
    (net (code "88") (name "unconnected-(AM3352-SOM-EVB-PLATFORM-AIN5-Pad4-37)") (class "Default")
      (node (ref "AM3352-SOM-EVB-PLATFORM") (pin "4-37") (pinfunction "AIN5_4-37") (pintype "passive"))
    )
    (net (code "89") (name "unconnected-(AM3352-SOM-EVB-PLATFORM-AIN6-Pad4-38)") (class "Default")
      (node (ref "AM3352-SOM-EVB-PLATFORM") (pin "4-38") (pinfunction "AIN6_4-38") (pintype "passive"))
    )
    (net (code "90") (name "unconnected-(AM3352-SOM-EVB-PLATFORM-AIN7-Pad4-36)") (class "Default")
      (node (ref "AM3352-SOM-EVB-PLATFORM") (pin "4-36") (pinfunction "AIN7_4-36") (pintype "passive"))
    )
    (net (code "91") (name "unconnected-(AM3352-SOM-EVB-PLATFORM-JTAG_TCK-Pad4-29)") (class "Default")
      (node (ref "AM3352-SOM-EVB-PLATFORM") (pin "4-29") (pinfunction "JTAG_TCK_4-29") (pintype "passive"))
    )
    (net (code "92") (name "unconnected-(AM3352-SOM-EVB-PLATFORM-JTAG_TDI-Pad4-31)") (class "Default")
      (node (ref "AM3352-SOM-EVB-PLATFORM") (pin "4-31") (pinfunction "JTAG_TDI_4-31") (pintype "passive"))
    )
    (net (code "93") (name "unconnected-(AM3352-SOM-EVB-PLATFORM-JTAG_TDO-Pad4-33)") (class "Default")
      (node (ref "AM3352-SOM-EVB-PLATFORM") (pin "4-33") (pinfunction "JTAG_TDO_4-33") (pintype "passive"))
    )
    (net (code "94") (name "unconnected-(AM3352-SOM-EVB-PLATFORM-JTAG_TMS-Pad4-32)") (class "Default")
      (node (ref "AM3352-SOM-EVB-PLATFORM") (pin "4-32") (pinfunction "JTAG_TMS_4-32") (pintype "passive"))
    )
    (net (code "95") (name "unconnected-(AM3352-SOM-EVB-PLATFORM-JTAG_TRST-Pad4-30)") (class "Default")
      (node (ref "AM3352-SOM-EVB-PLATFORM") (pin "4-30") (pinfunction "JTAG_TRST_4-30") (pintype "passive"))
    )
    (net (code "96") (name "unconnected-(AM3352-SOM-EVB-PLATFORM-MMC0-SDCD#{slash}EMU4-Pad3-17)") (class "Default")
      (node (ref "AM3352-SOM-EVB-PLATFORM") (pin "3-17") (pinfunction "MMC0-SDCD#/EMU4_3-17") (pintype "passive"))
    )
    (net (code "97") (name "unconnected-(AM3352-SOM-EVB-PLATFORM-NNMI-Pad3-22)") (class "Default")
      (node (ref "AM3352-SOM-EVB-PLATFORM") (pin "3-22") (pinfunction "NNMI_3-22") (pintype "passive"))
    )
    (net (code "98") (name "unconnected-(AM3352-SOM-EVB-PLATFORM-P0_0{slash}EMDIO-Pad3-38)") (class "Default")
      (node (ref "AM3352-SOM-EVB-PLATFORM") (pin "3-38") (pinfunction "P0_0/EMDIO_3-38") (pintype "passive"))
    )
    (net (code "99") (name "unconnected-(AM3352-SOM-EVB-PLATFORM-P0_1{slash}EMDC-Pad3-36)") (class "Default")
      (node (ref "AM3352-SOM-EVB-PLATFORM") (pin "3-36") (pinfunction "P0_1/EMDC_3-36") (pintype "passive"))
    )
    (net (code "100") (name "unconnected-(AM3352-SOM-EVB-PLATFORM-P0_2{slash}SPI0_SCLK-Pad4-11)") (class "Default")
      (node (ref "AM3352-SOM-EVB-PLATFORM") (pin "4-11") (pinfunction "P0_2/SPI0_SCLK_4-11") (pintype "passive"))
    )
    (net (code "101") (name "unconnected-(AM3352-SOM-EVB-PLATFORM-P0_3{slash}SPI0_D0(MISO)-Pad4-9)") (class "Default")
      (node (ref "AM3352-SOM-EVB-PLATFORM") (pin "4-9") (pinfunction "P0_3/SPI0_D0(MISO)_4-9") (pintype "passive"))
    )
    (net (code "102") (name "unconnected-(AM3352-SOM-EVB-PLATFORM-P0_4{slash}SPI0_D1(MOSI)-Pad4-10)") (class "Default")
      (node (ref "AM3352-SOM-EVB-PLATFORM") (pin "4-10") (pinfunction "P0_4/SPI0_D1(MOSI)_4-10") (pintype "passive"))
    )
    (net (code "103") (name "unconnected-(AM3352-SOM-EVB-PLATFORM-P0_5{slash}SPI0_CS0-Pad4-12)") (class "Default")
      (node (ref "AM3352-SOM-EVB-PLATFORM") (pin "4-12") (pinfunction "P0_5/SPI0_CS0_4-12") (pintype "passive"))
    )
    (net (code "104") (name "unconnected-(AM3352-SOM-EVB-PLATFORM-P0_7{slash}PWM0_OUT-Pad4-27)") (class "Default")
      (node (ref "AM3352-SOM-EVB-PLATFORM") (pin "4-27") (pinfunction "P0_7/PWM0_OUT_4-27") (pintype "passive"))
    )
    (net (code "105") (name "unconnected-(AM3352-SOM-EVB-PLATFORM-P0_14{slash}UART1_RXD-Pad4-6)") (class "Default")
      (node (ref "AM3352-SOM-EVB-PLATFORM") (pin "4-6") (pinfunction "P0_14/UART1_RXD_4-6") (pintype "passive"))
    )
    (net (code "106") (name "unconnected-(AM3352-SOM-EVB-PLATFORM-P0_15{slash}UART1_TXD-Pad4-5)") (class "Default")
      (node (ref "AM3352-SOM-EVB-PLATFORM") (pin "4-5") (pinfunction "P0_15/UART1_TXD_4-5") (pintype "passive"))
    )
    (net (code "107") (name "unconnected-(AM3352-SOM-EVB-PLATFORM-P0_16{slash}ETXD3-Pad3-29)") (class "Default")
      (node (ref "AM3352-SOM-EVB-PLATFORM") (pin "3-29") (pinfunction "P0_16/ETXD3_3-29") (pintype "passive"))
    )
    (net (code "108") (name "unconnected-(AM3352-SOM-EVB-PLATFORM-P0_17{slash}ETXD2-Pad3-27)") (class "Default")
      (node (ref "AM3352-SOM-EVB-PLATFORM") (pin "3-27") (pinfunction "P0_17/ETXD2_3-27") (pintype "passive"))
    )
    (net (code "109") (name "unconnected-(AM3352-SOM-EVB-PLATFORM-P0_20{slash}EMU3-Pad4-22)") (class "Default")
      (node (ref "AM3352-SOM-EVB-PLATFORM") (pin "4-22") (pinfunction "P0_20/EMU3_4-22") (pintype "passive"))
    )
    (net (code "110") (name "unconnected-(AM3352-SOM-EVB-PLATFORM-P0_21{slash}ETXD1-Pad3-25)") (class "Default")
      (node (ref "AM3352-SOM-EVB-PLATFORM") (pin "3-25") (pinfunction "P0_21/ETXD1_3-25") (pintype "passive"))
    )
    (net (code "111") (name "unconnected-(AM3352-SOM-EVB-PLATFORM-P0_28{slash}ETXD0-Pad3-23)") (class "Default")
      (node (ref "AM3352-SOM-EVB-PLATFORM") (pin "3-23") (pinfunction "P0_28/ETXD0_3-23") (pintype "passive"))
    )
    (net (code "112") (name "unconnected-(AM3352-SOM-EVB-PLATFORM-P0_29{slash}EPHY-RST#{slash}RFCLK-Pad3-40)") (class "Default")
      (node (ref "AM3352-SOM-EVB-PLATFORM") (pin "3-40") (pinfunction "P0_29/EPHY-RST#/RFCLK_3-40") (pintype "passive"))
    )
    (net (code "113") (name "unconnected-(AM3352-SOM-EVB-PLATFORM-P2_18{slash}ERXD3-Pad3-30)") (class "Default")
      (node (ref "AM3352-SOM-EVB-PLATFORM") (pin "3-30") (pinfunction "P2_18/ERXD3_3-30") (pintype "passive"))
    )
    (net (code "114") (name "unconnected-(AM3352-SOM-EVB-PLATFORM-P2_19{slash}ERXD2-Pad3-28)") (class "Default")
      (node (ref "AM3352-SOM-EVB-PLATFORM") (pin "3-28") (pinfunction "P2_19/ERXD2_3-28") (pintype "passive"))
    )
    (net (code "115") (name "unconnected-(AM3352-SOM-EVB-PLATFORM-P2_20{slash}ERXD1-Pad3-26)") (class "Default")
      (node (ref "AM3352-SOM-EVB-PLATFORM") (pin "3-26") (pinfunction "P2_20/ERXD1_3-26") (pintype "passive"))
    )
    (net (code "116") (name "unconnected-(AM3352-SOM-EVB-PLATFORM-P2_21{slash}ERXD0-Pad3-24)") (class "Default")
      (node (ref "AM3352-SOM-EVB-PLATFORM") (pin "3-24") (pinfunction "P2_21/ERXD0_3-24") (pintype "passive"))
    )
    (net (code "117") (name "unconnected-(AM3352-SOM-EVB-PLATFORM-P3_0{slash}ECOL-Pad3-37)") (class "Default")
      (node (ref "AM3352-SOM-EVB-PLATFORM") (pin "3-37") (pinfunction "P3_0/ECOL_3-37") (pintype "passive"))
    )
    (net (code "118") (name "unconnected-(AM3352-SOM-EVB-PLATFORM-P3_1{slash}ECRS-Pad3-39)") (class "Default")
      (node (ref "AM3352-SOM-EVB-PLATFORM") (pin "3-39") (pinfunction "P3_1/ECRS_3-39") (pintype "passive"))
    )
    (net (code "119") (name "unconnected-(AM3352-SOM-EVB-PLATFORM-P3_2{slash}ERXERR-Pad3-35)") (class "Default")
      (node (ref "AM3352-SOM-EVB-PLATFORM") (pin "3-35") (pinfunction "P3_2/ERXERR_3-35") (pintype "passive"))
    )
    (net (code "120") (name "unconnected-(AM3352-SOM-EVB-PLATFORM-P3_3{slash}ETXEN-Pad3-31)") (class "Default")
      (node (ref "AM3352-SOM-EVB-PLATFORM") (pin "3-31") (pinfunction "P3_3/ETXEN_3-31") (pintype "passive"))
    )
    (net (code "121") (name "unconnected-(AM3352-SOM-EVB-PLATFORM-P3_4{slash}ERXDV-Pad3-32)") (class "Default")
      (node (ref "AM3352-SOM-EVB-PLATFORM") (pin "3-32") (pinfunction "P3_4/ERXDV_3-32") (pintype "passive"))
    )
    (net (code "122") (name "unconnected-(AM3352-SOM-EVB-PLATFORM-P3_9{slash}ETXCK-Pad3-33)") (class "Default")
      (node (ref "AM3352-SOM-EVB-PLATFORM") (pin "3-33") (pinfunction "P3_9/ETXCK_3-33") (pintype "passive"))
    )
    (net (code "123") (name "unconnected-(AM3352-SOM-EVB-PLATFORM-P3_10{slash}ERXCK-Pad3-34)") (class "Default")
      (node (ref "AM3352-SOM-EVB-PLATFORM") (pin "3-34") (pinfunction "P3_10/ERXCK_3-34") (pintype "passive"))
    )
    (net (code "124") (name "unconnected-(AM3352-SOM-EVB-PLATFORM-PMIC_POWER_EN-Pad3-18)") (class "Default")
      (node (ref "AM3352-SOM-EVB-PLATFORM") (pin "3-18") (pinfunction "PMIC_POWER_EN_3-18") (pintype "passive"))
    )
    (net (code "125") (name "unconnected-(AM3352-SOM-EVB-PLATFORM-PWRONRSTN-Pad3-19)") (class "Default")
      (node (ref "AM3352-SOM-EVB-PLATFORM") (pin "3-19") (pinfunction "PWRONRSTN_3-19") (pintype "passive"))
    )
    (net (code "126") (name "unconnected-(AM3352-SOM-EVB-PLATFORM-SYS_RESETN-Pad3-21)") (class "Default")
      (node (ref "AM3352-SOM-EVB-PLATFORM") (pin "3-21") (pinfunction "SYS_RESETN_3-21") (pintype "passive"))
    )
    (net (code "127") (name "unconnected-(AM3352-SOM-EVB-PLATFORM-VDDA_ADC-Pad4-39)") (class "Default")
      (node (ref "AM3352-SOM-EVB-PLATFORM") (pin "4-39") (pinfunction "VDDA_ADC_4-39") (pintype "passive"))
    )
    (net (code "128") (name "unconnected-(AM3352-SOM-EVB-PLATFORM-VREFP-Pad4-34)") (class "Default")
      (node (ref "AM3352-SOM-EVB-PLATFORM") (pin "4-34") (pinfunction "VREFP_4-34") (pintype "passive"))
    )
    (net (code "129") (name "unconnected-(IC1-NC-Pad2)") (class "Default")
      (node (ref "IC1") (pin "2") (pinfunction "NC_2") (pintype "no_connect"))
    )
    (net (code "130") (name "unconnected-(IC1-V_REF-Pad14)") (class "Default")
      (node (ref "IC1") (pin "14") (pinfunction "V_REF_14") (pintype "output"))
    )
    (net (code "131") (name "unconnected-(IC2-NC-Pad2)") (class "Default")
      (node (ref "IC2") (pin "2") (pinfunction "NC_2") (pintype "no_connect"))
    )
    (net (code "132") (name "unconnected-(IC2-V_REF-Pad14)") (class "Default")
      (node (ref "IC2") (pin "14") (pinfunction "V_REF_14") (pintype "output"))
    )
    (net (code "133") (name "unconnected-(IC3-32KHZ-Pad1)") (class "Default")
      (node (ref "IC3") (pin "1") (pinfunction "32KHZ_1") (pintype "bidirectional"))
    )
    (net (code "134") (name "unconnected-(OOBD2-CONNECTOR-Pad4)") (class "Default")
      (node (ref "OOBD2-CONNECTOR") (pin "4") (pinfunction "4_4") (pintype "passive"))
    )
    (net (code "135") (name "unconnected-(OOBD2-CONNECTOR-Pad5)") (class "Default")
      (node (ref "OOBD2-CONNECTOR") (pin "5") (pinfunction "5_5") (pintype "passive"))
    )
    (net (code "136") (name "unconnected-(OOBD2-CONNECTOR-Pad8)") (class "Default")
      (node (ref "OOBD2-CONNECTOR") (pin "8") (pinfunction "8_8") (pintype "passive"))
    )
    (net (code "137") (name "unconnected-(OOBD2-CONNECTOR-Pad9)") (class "Default")
      (node (ref "OOBD2-CONNECTOR") (pin "9") (pinfunction "9_9") (pintype "passive"))
    )
    (net (code "138") (name "unconnected-(OOBDPICAN-Pad3)") (class "Default")
      (node (ref "OOBDPICAN") (pin "3") (pinfunction "3_3") (pintype "passive"))
    )
    (net (code "139") (name "unconnected-(OOBDPICAN-Pad6)") (class "Default")
      (node (ref "OOBDPICAN") (pin "6") (pinfunction "6_6") (pintype "passive"))
    )
    (net (code "140") (name "unconnected-(TLV320AIC1-GPIO1-Pad32)") (class "Default")
      (node (ref "TLV320AIC1") (pin "32") (pinfunction "GPIO1_32") (pintype "bidirectional"))
    )
    (net (code "141") (name "unconnected-(TLV320AIC1-HPCOM-Pad15)") (class "Default")
      (node (ref "TLV320AIC1") (pin "15") (pinfunction "HPCOM_15") (pintype "bidirectional"))
    )
    (net (code "142") (name "unconnected-(TLV320AIC1-HPLOUT-Pad14)") (class "Default")
      (node (ref "TLV320AIC1") (pin "14") (pinfunction "HPLOUT_14") (pintype "bidirectional"))
    )
    (net (code "143") (name "unconnected-(TLV320AIC1-HPROUT-Pad17)") (class "Default")
      (node (ref "TLV320AIC1") (pin "17") (pinfunction "HPROUT_17") (pintype "bidirectional"))
    )
    (net (code "144") (name "unconnected-(TLV320AIC1-LINE1LP-Pad4)") (class "Default")
      (node (ref "TLV320AIC1") (pin "4") (pinfunction "LINE1LP_4") (pintype "bidirectional"))
    )
    (net (code "145") (name "unconnected-(TLV320AIC1-LINE1RP-Pad5)") (class "Default")
      (node (ref "TLV320AIC1") (pin "5") (pinfunction "LINE1RP_5") (pintype "bidirectional"))
    )
    (net (code "146") (name "unconnected-(TLV320AIC1-LINE2LP-Pad7)") (class "Default")
      (node (ref "TLV320AIC1") (pin "7") (pinfunction "LINE2LP_7") (pintype "bidirectional"))
    )
    (net (code "147") (name "unconnected-(TLV320AIC1-LINE2RP{slash}LINE2LM-Pad8)") (class "Default")
      (node (ref "TLV320AIC1") (pin "8") (pinfunction "LINE2RP/LINE2LM_8") (pintype "bidirectional"))
    )
    (net (code "148") (name "unconnected-(TLV320AIC1-MIC3L{slash}LINE1RM-Pad6)") (class "Default")
      (node (ref "TLV320AIC1") (pin "6") (pinfunction "MIC3L/LINE1RM_6") (pintype "bidirectional"))
    )
    (net (code "149") (name "unconnected-(TLV320AIC1-MIC3R{slash}LINE2RM-Pad9)") (class "Default")
      (node (ref "TLV320AIC1") (pin "9") (pinfunction "MIC3R/LINE2RM_9") (pintype "bidirectional"))
    )
    (net (code "150") (name "unconnected-(TLV320AIC1-MICBIAS-Pad10)") (class "Default")
      (node (ref "TLV320AIC1") (pin "10") (pinfunction "MICBIAS_10") (pintype "bidirectional"))
    )
    (net (code "151") (name "unconnected-(TLV320AIC1-MICDET{slash}LINE1LM-Pad3)") (class "Default")
      (node (ref "TLV320AIC1") (pin "3") (pinfunction "MICDET/LINE1LM_3") (pintype "bidirectional"))
    )
    (net (code "152") (name "unconnected-(TLV320AIC1-SWOUTM-Pad28)") (class "Default")
      (node (ref "TLV320AIC1") (pin "28") (pinfunction "SWOUTM_28") (pintype "bidirectional"))
    )
    (net (code "153") (name "unconnected-(TLV320AIC1-SWOUTP-Pad29)") (class "Default")
      (node (ref "TLV320AIC1") (pin "29") (pinfunction "SWOUTP_29") (pintype "bidirectional"))
    )
    (net (code "154") (name "unconnected-(U1-VREF-Pad5)") (class "Default")
      (node (ref "U1") (pin "5") (pinfunction "VREF_5") (pintype "output"))
    )
    (net (code "155") (name "unconnected-(U2-VREF-Pad5)") (class "Default")
      (node (ref "U2") (pin "5") (pinfunction "VREF_5") (pintype "output"))
    )
  )
)
